# Fuel_Cell_Controller_V1.net
KiCad netlist of a schematic drawn in EAGLE
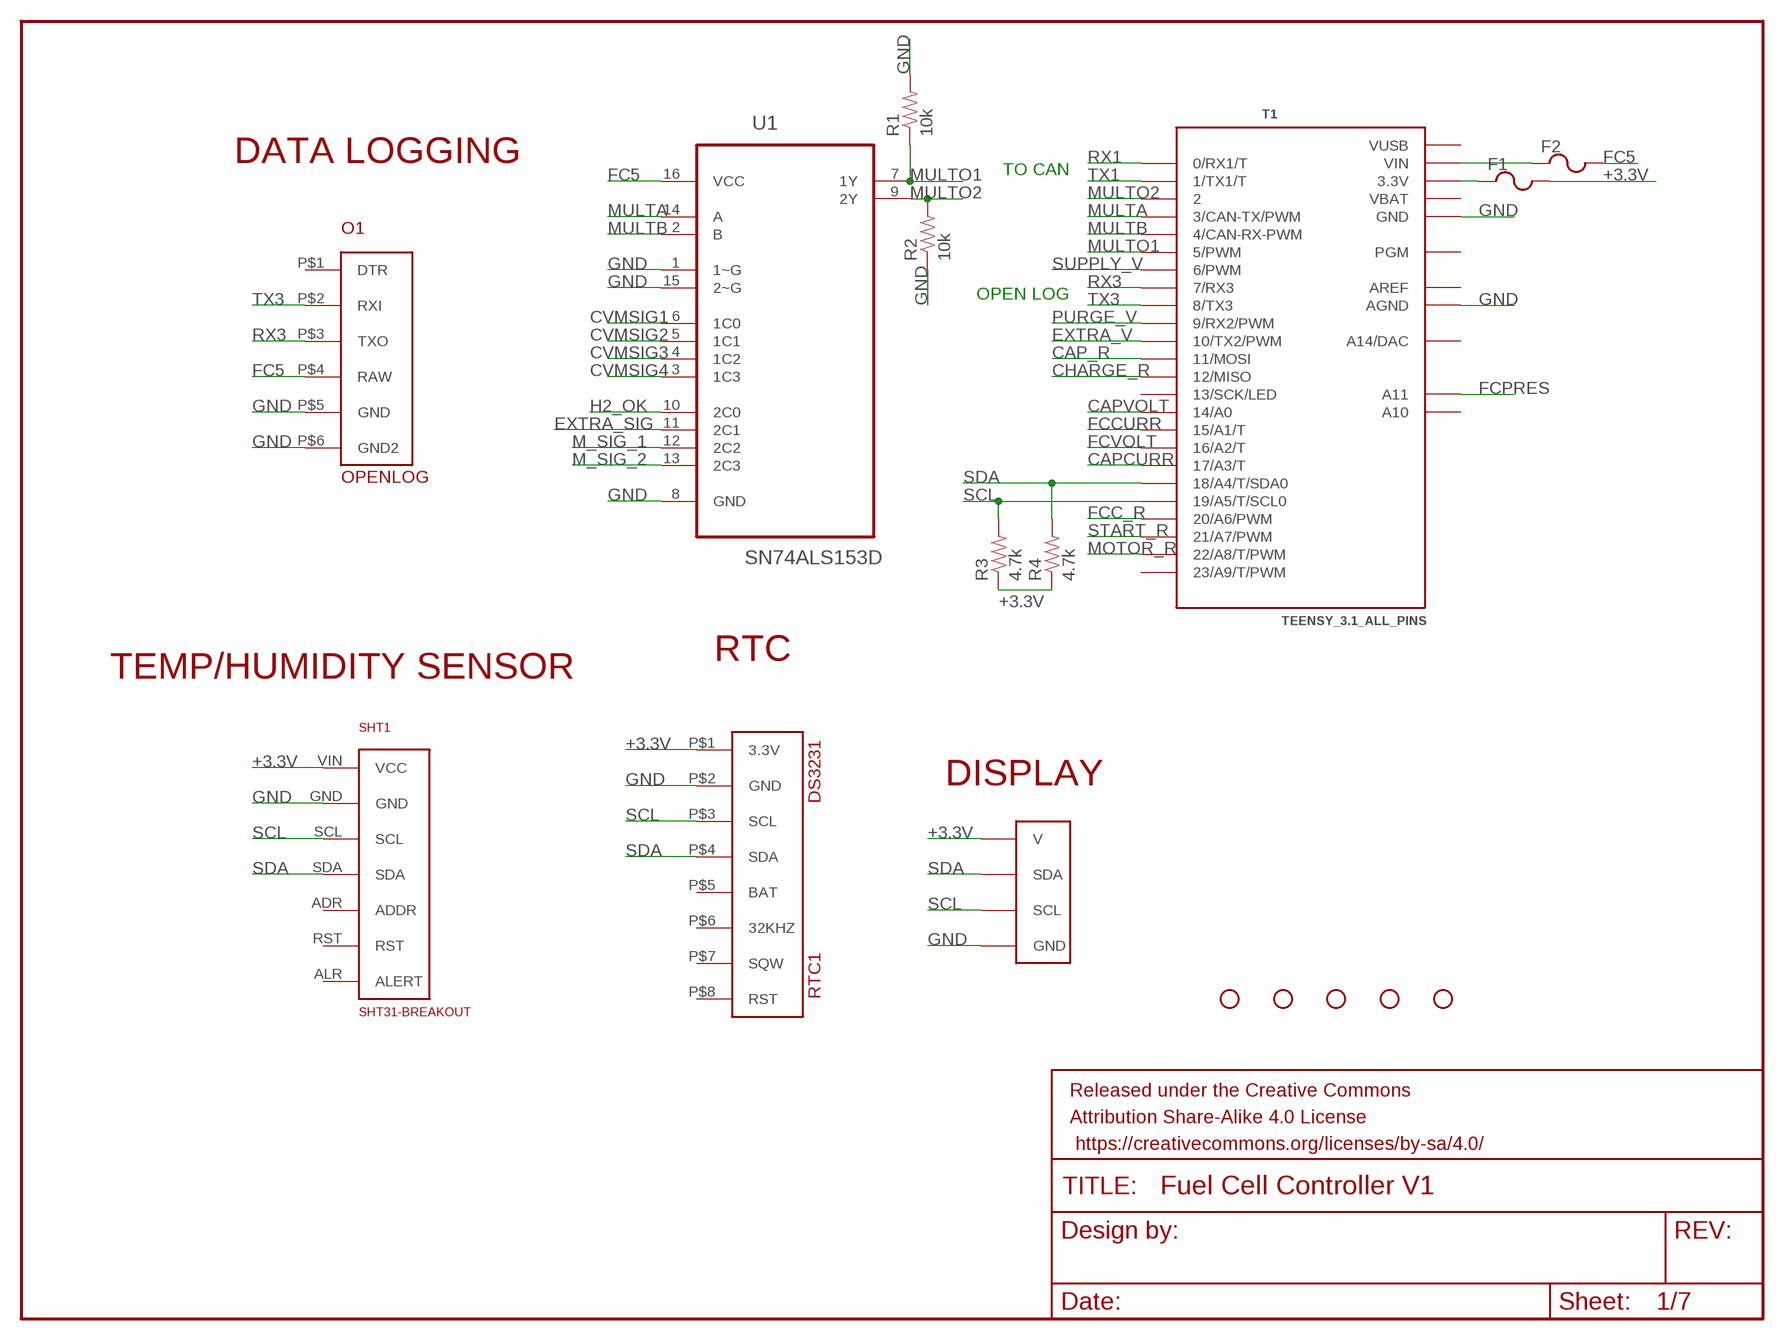
[diagram p0: schematic, sheet 1]
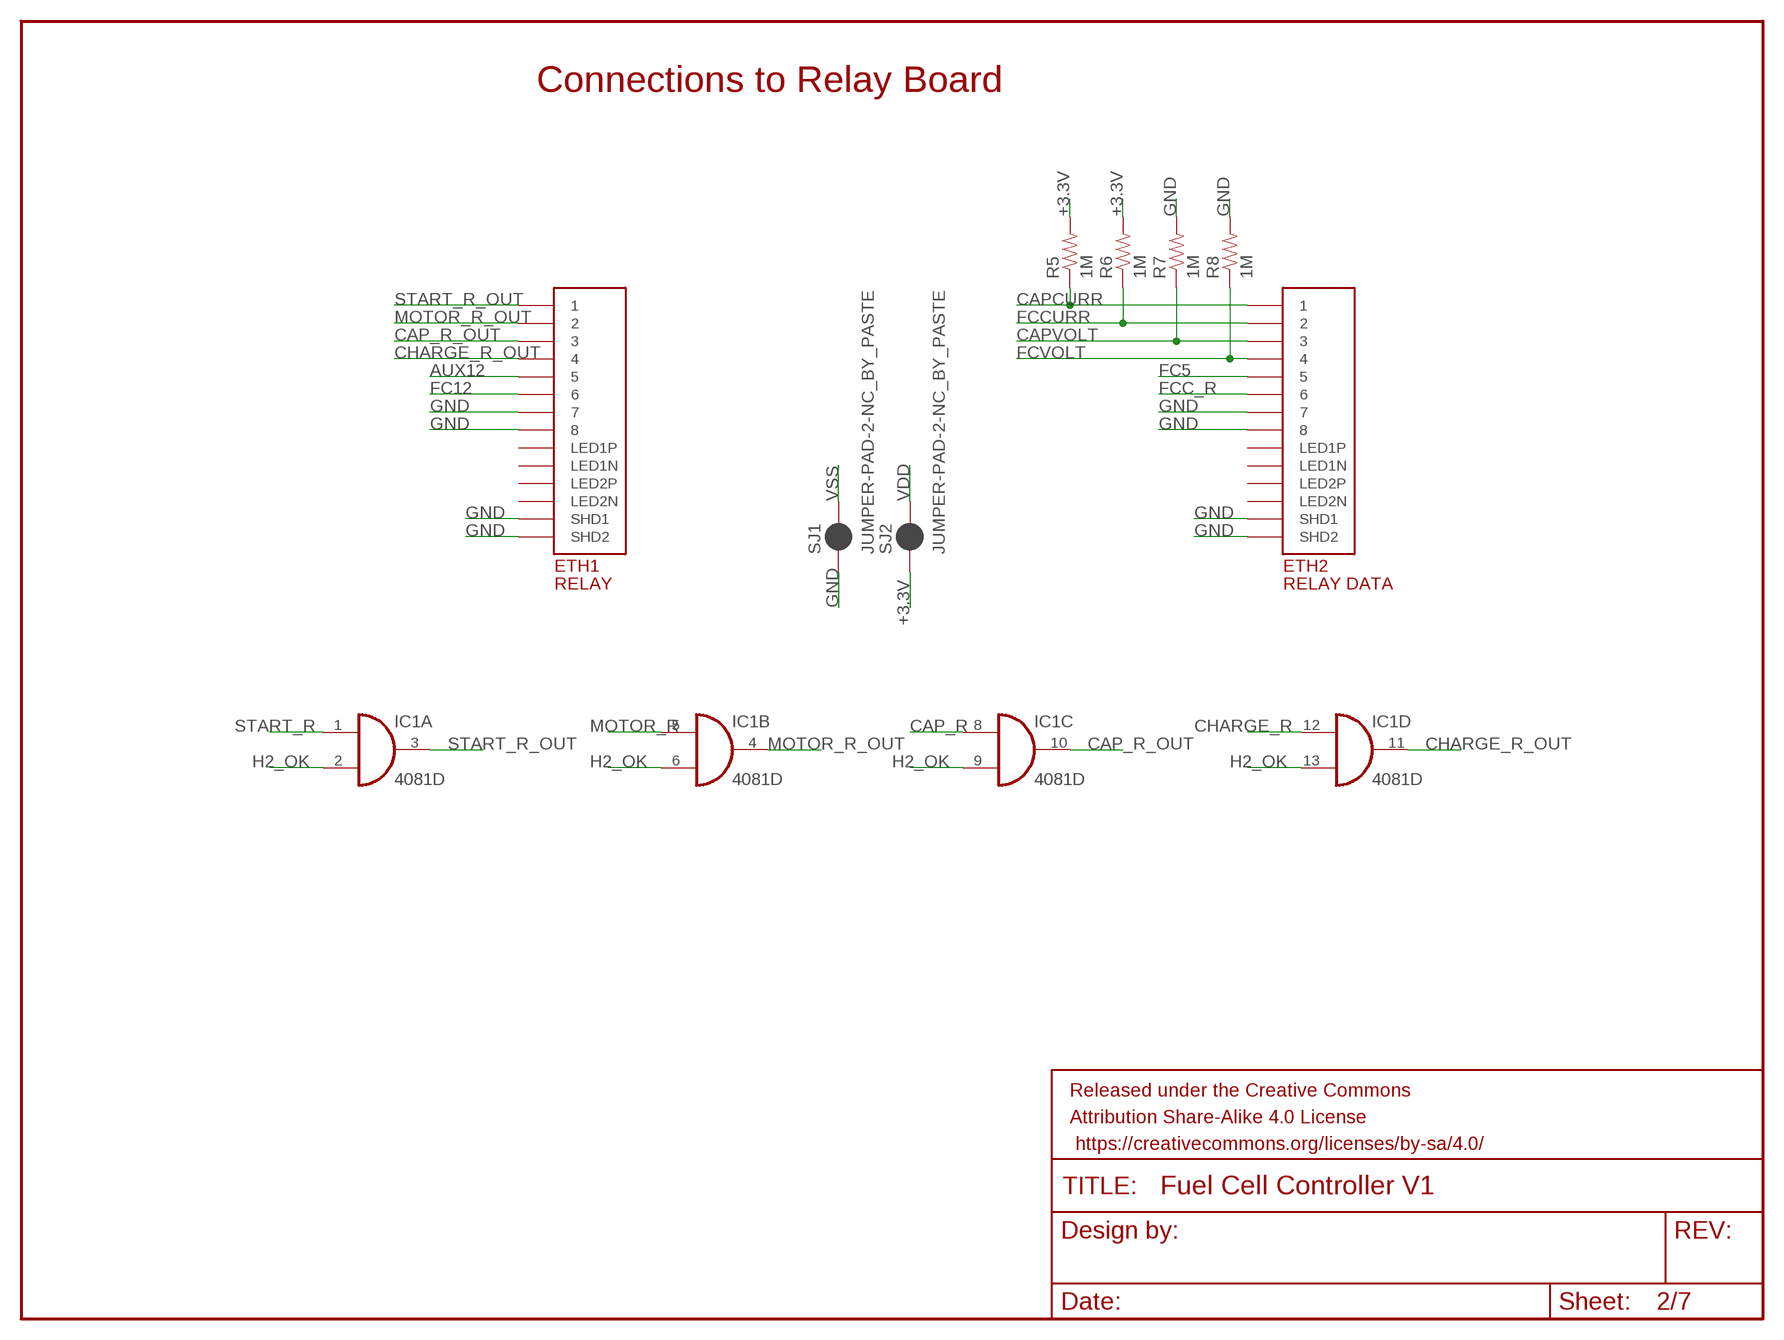
[diagram p1: schematic, sheet 2]
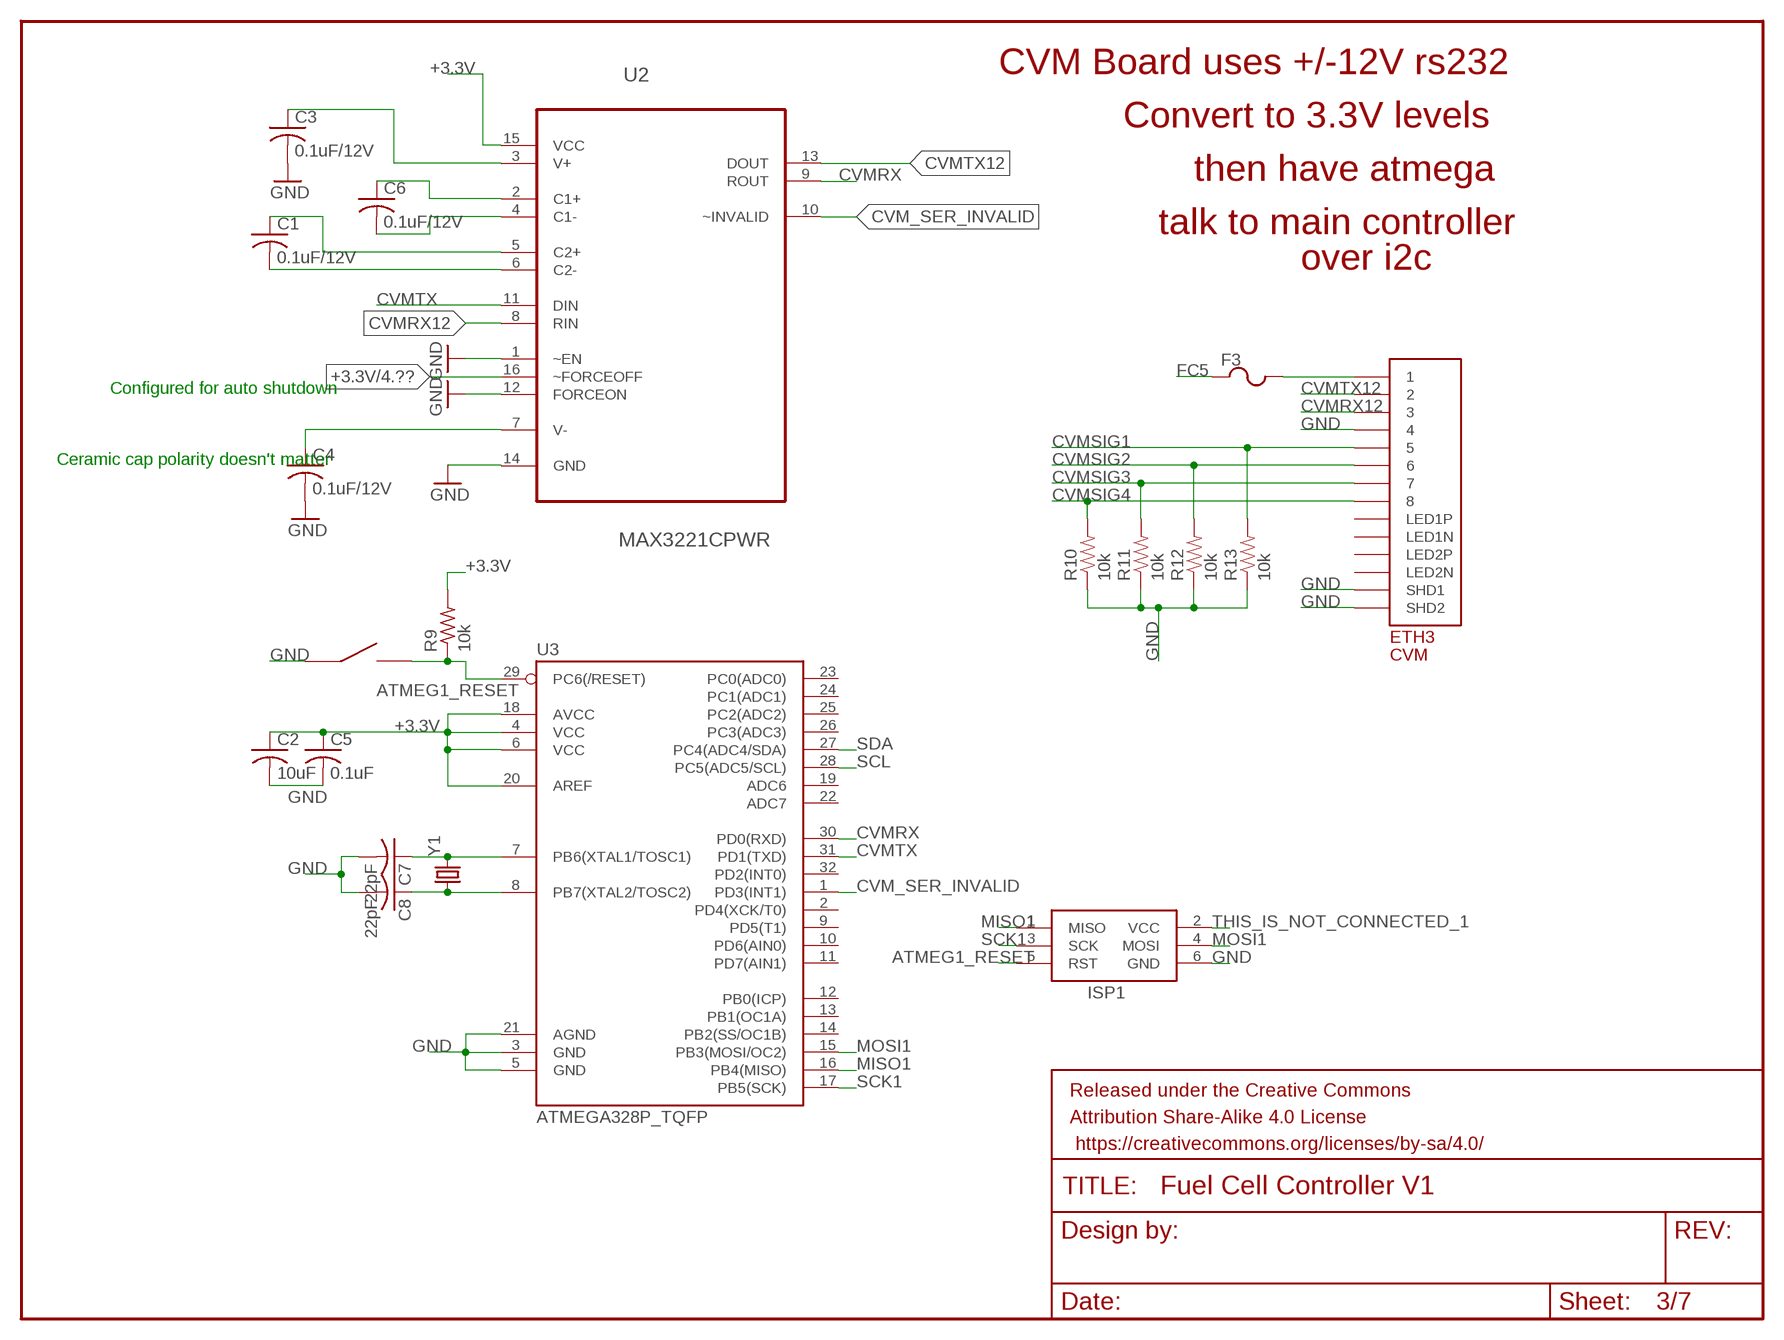
[diagram p2: schematic, sheet 3]
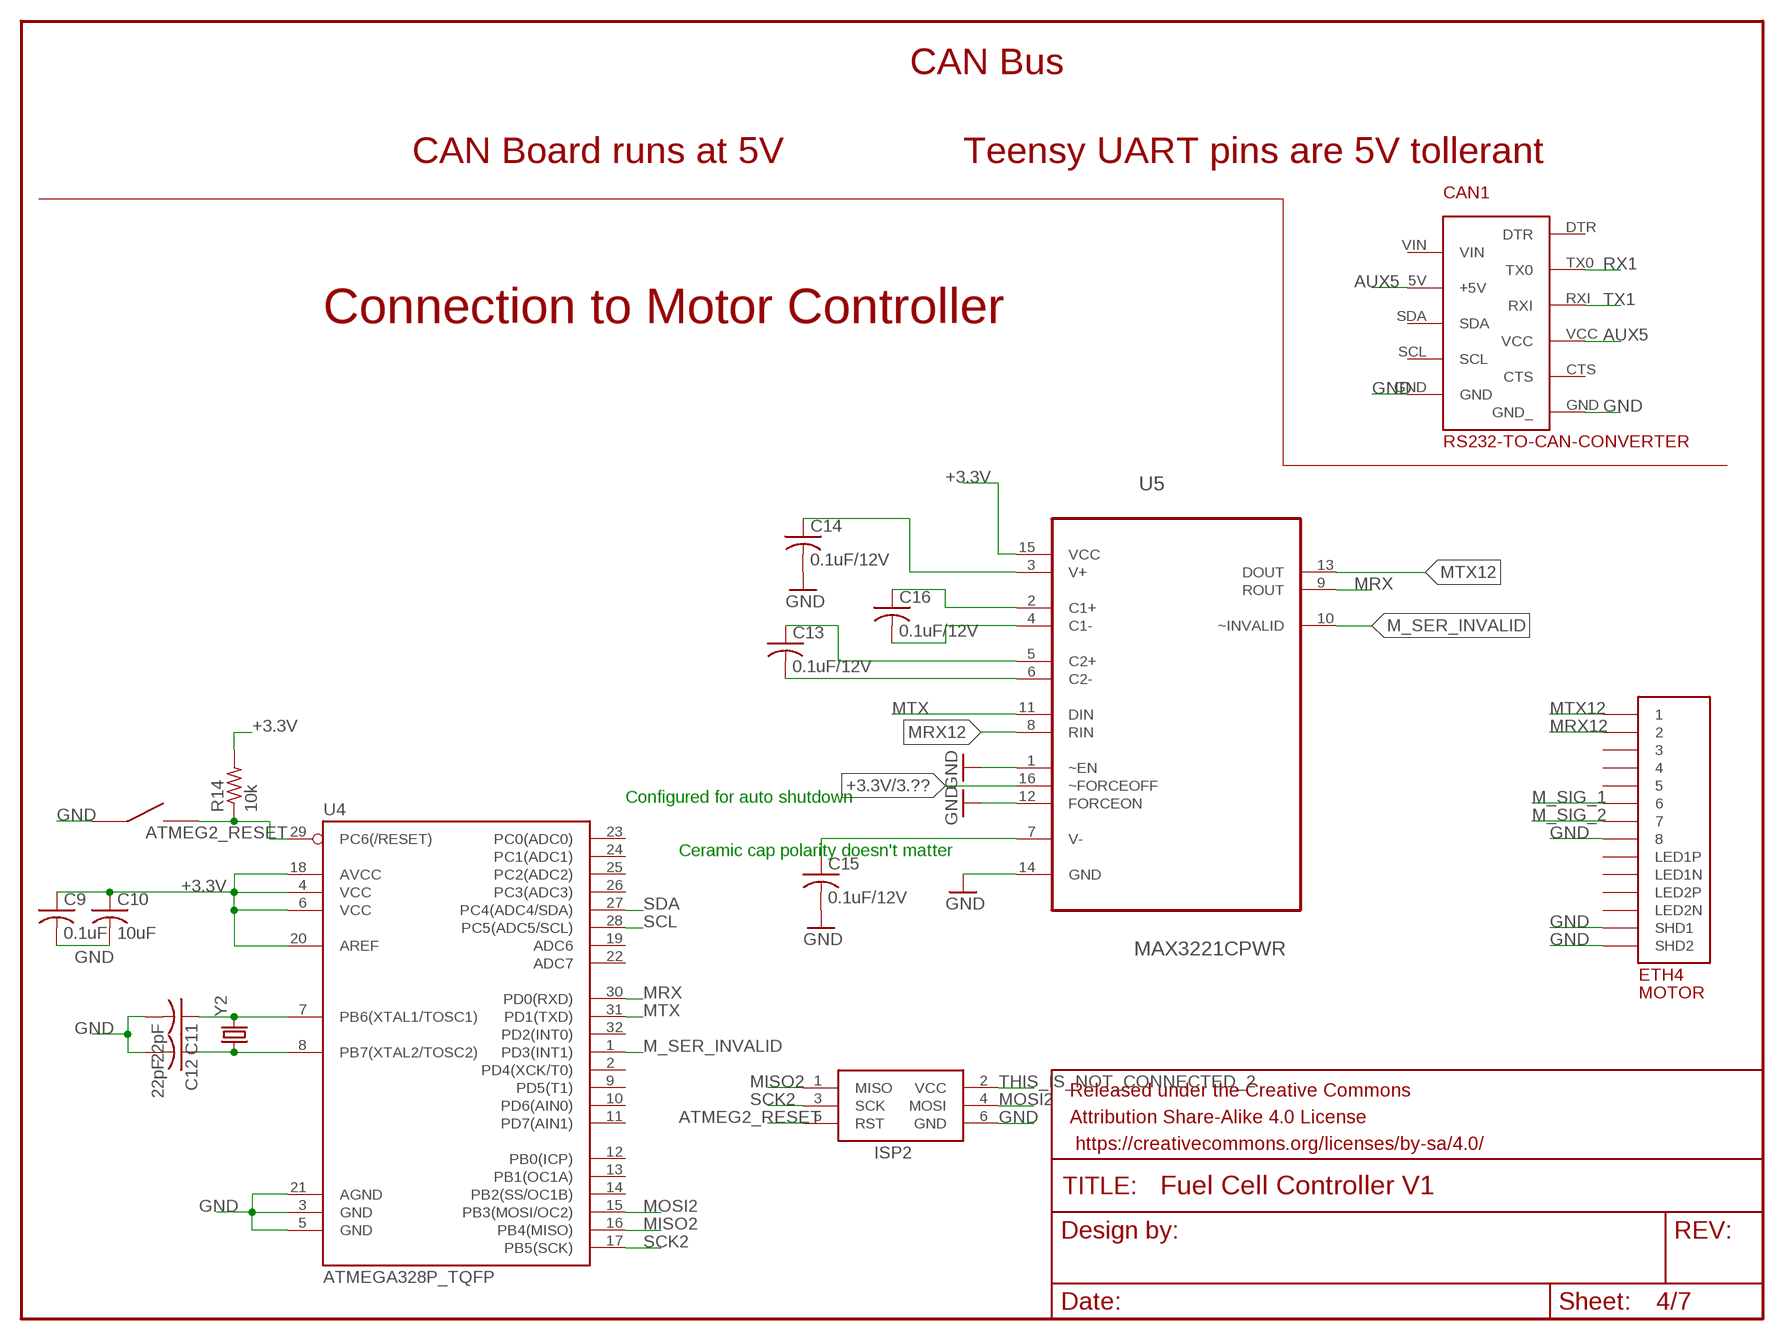
[diagram p3: schematic, sheet 4]
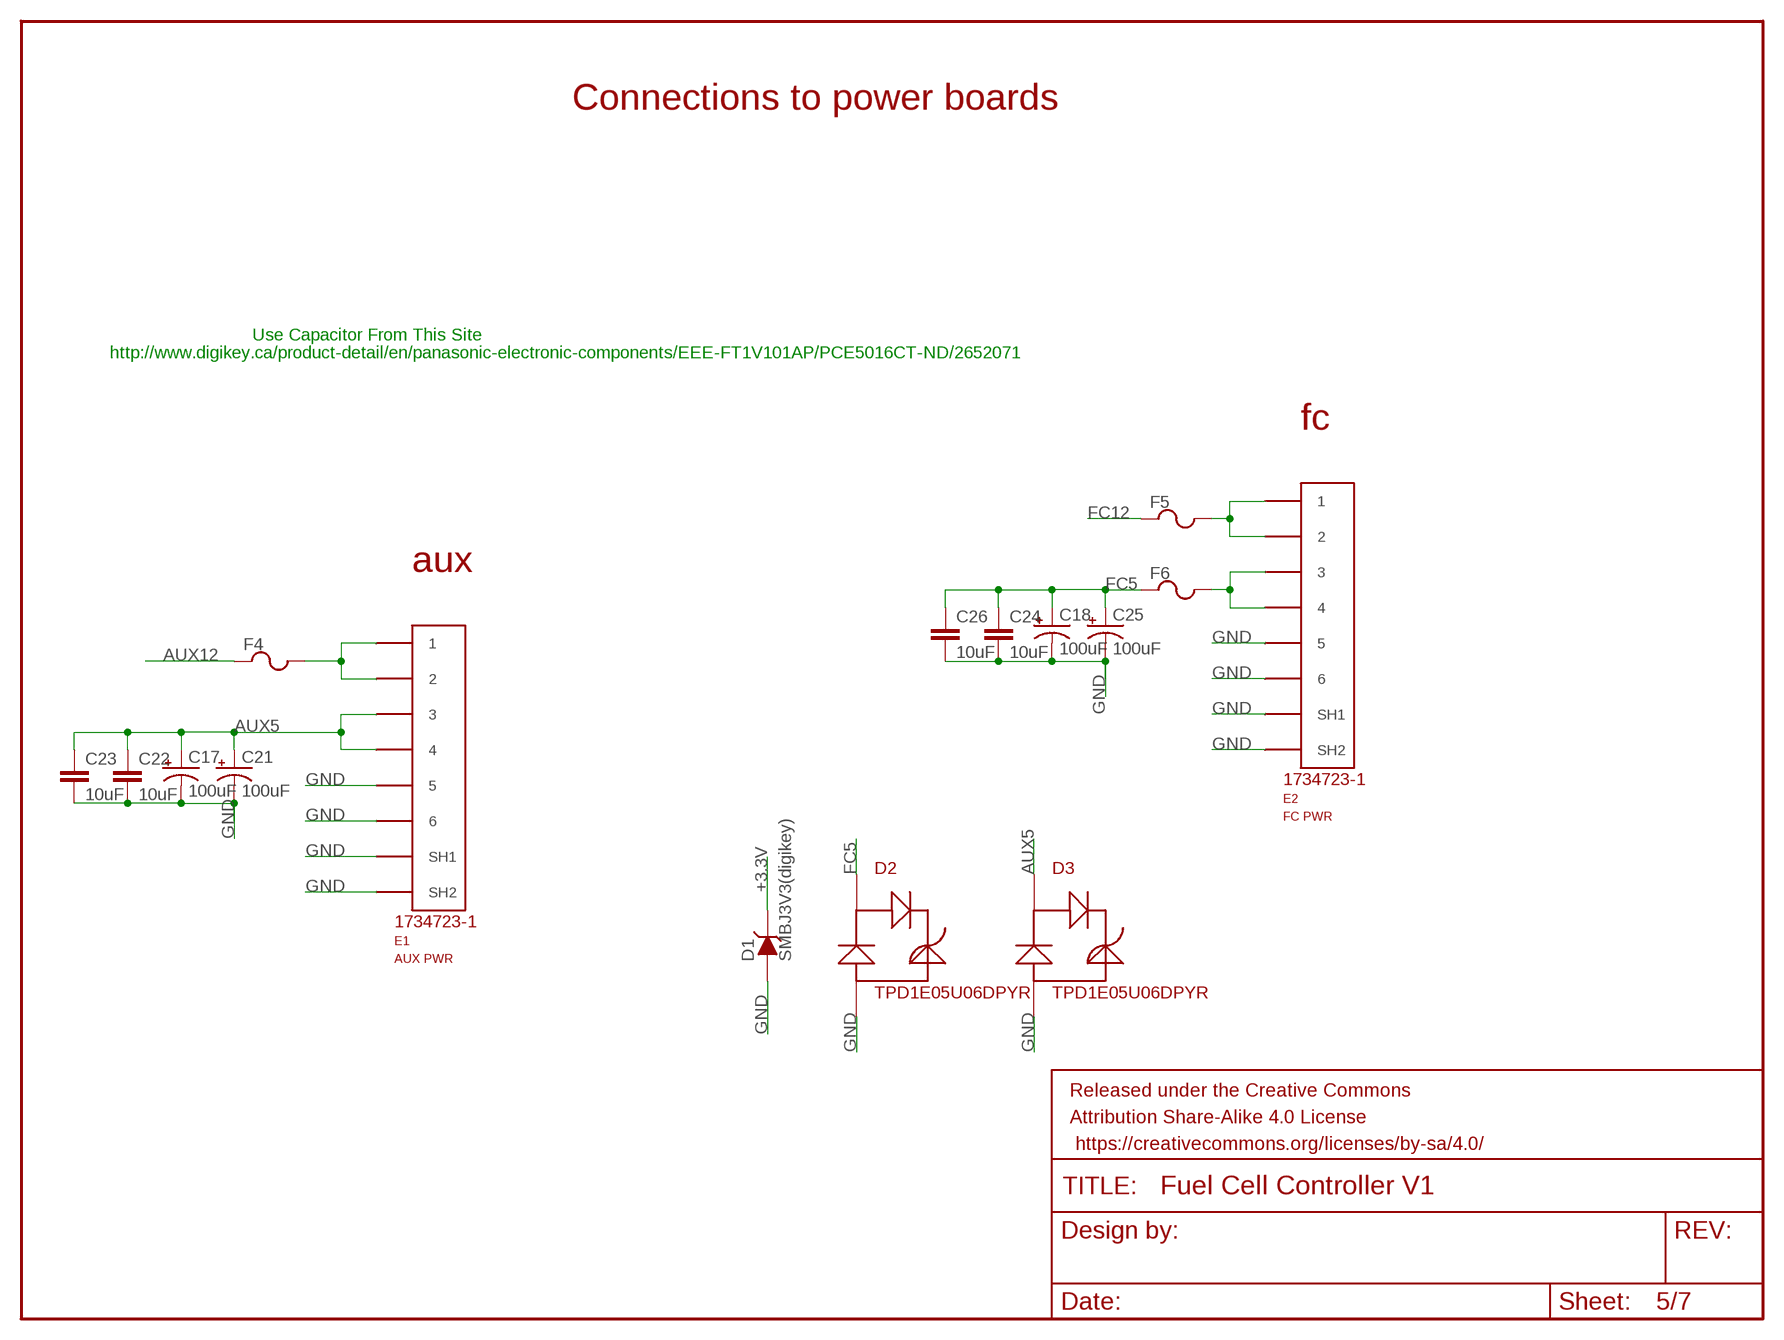
[diagram p4: schematic, sheet 5]
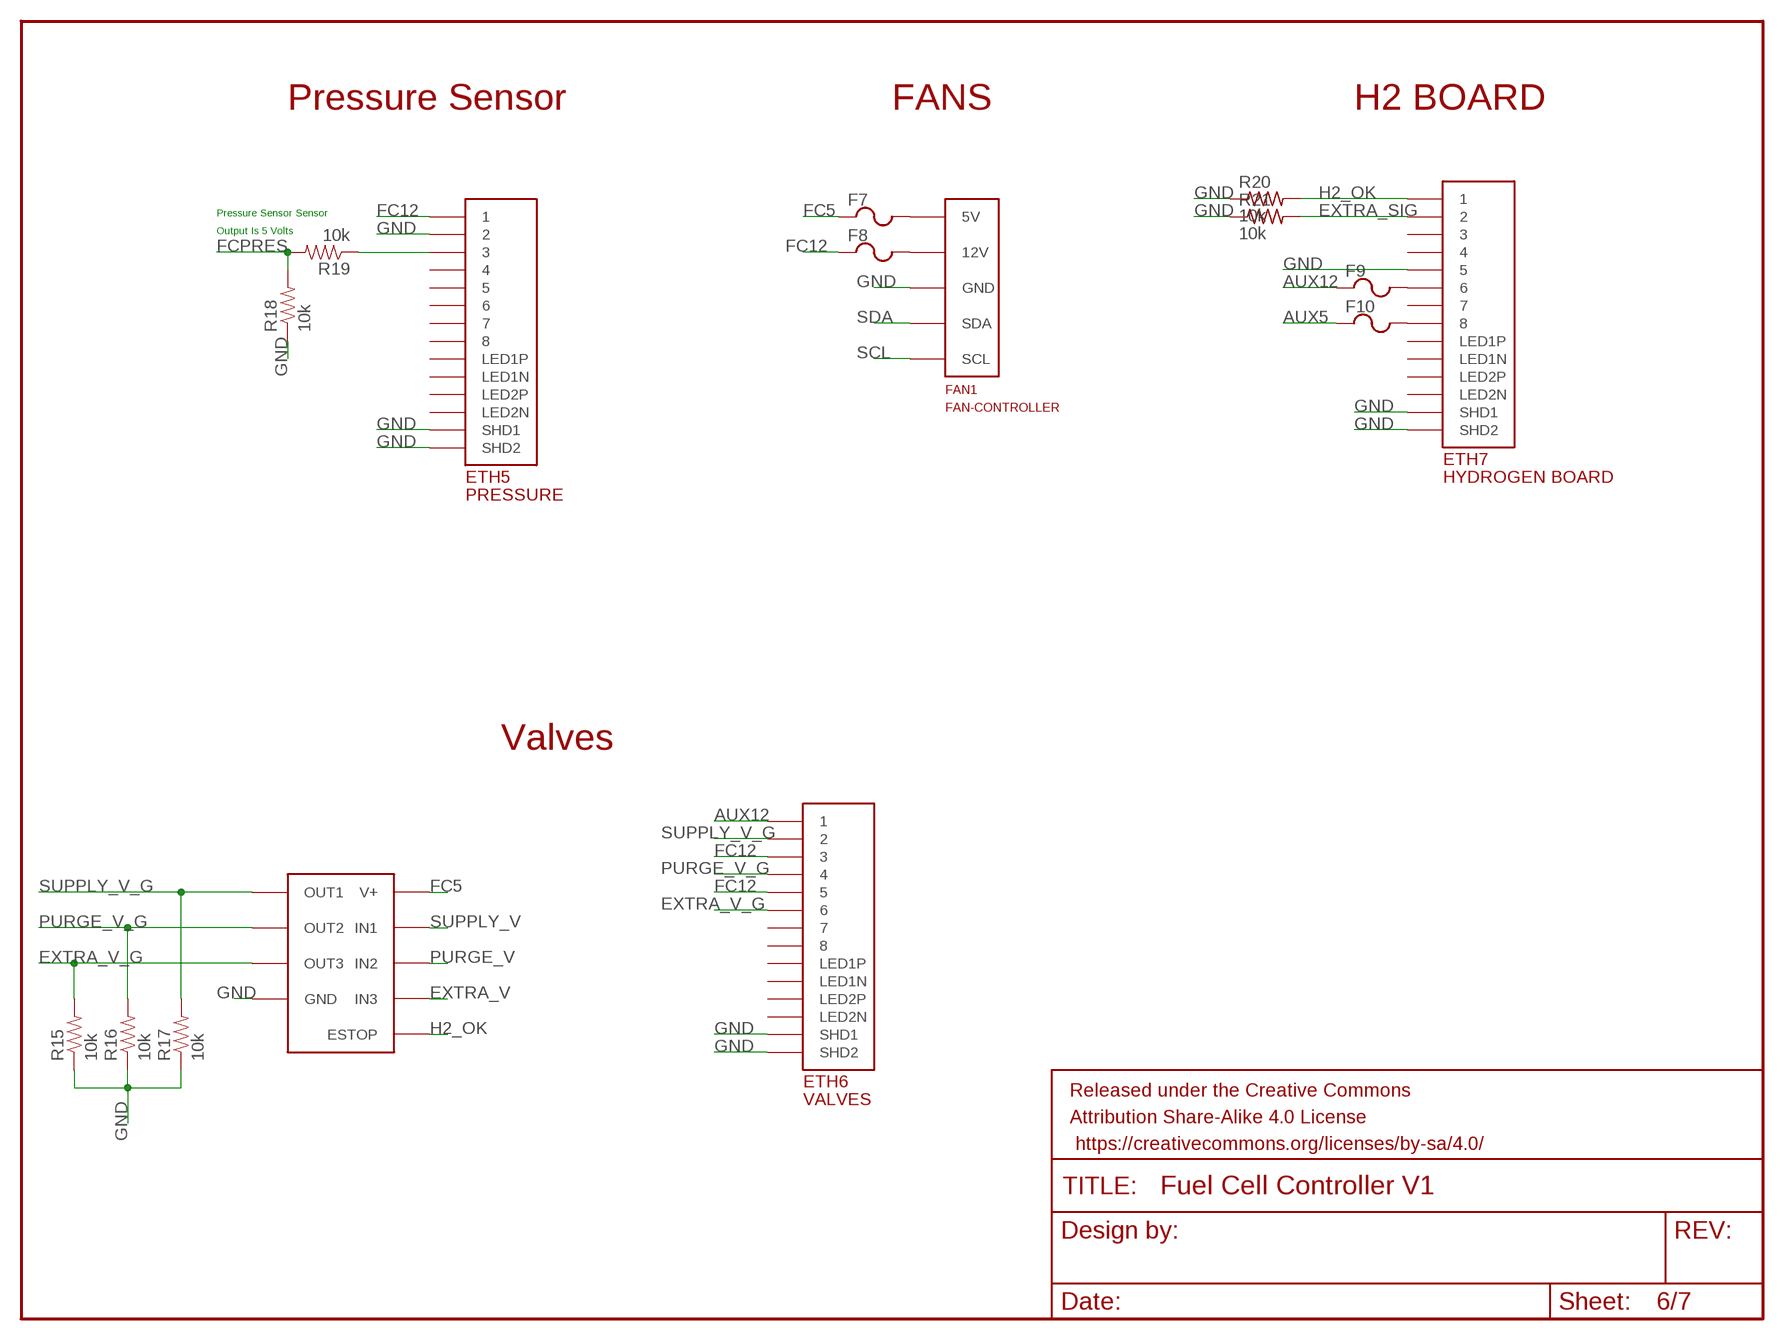
[diagram p5: schematic, sheet 6]
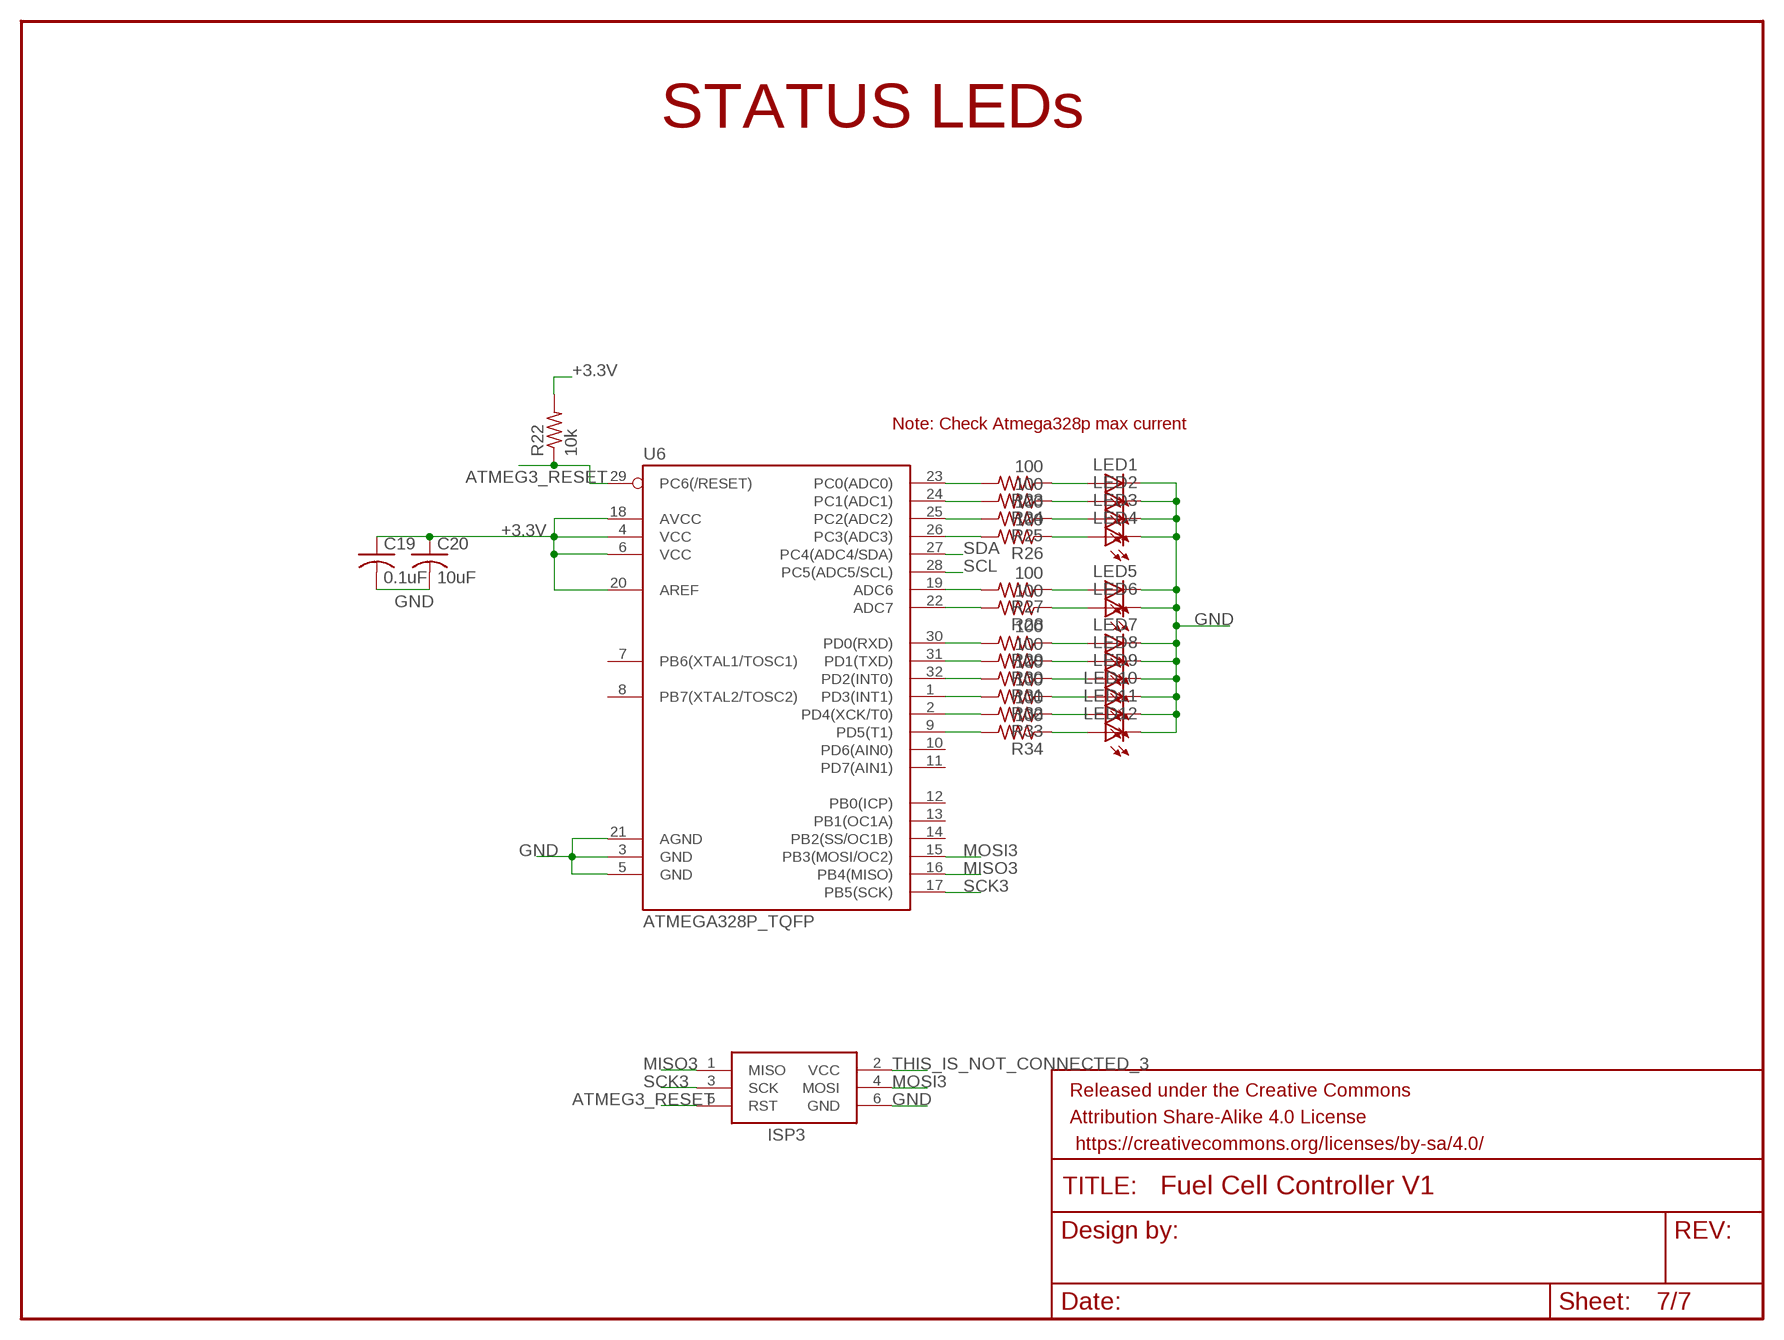
[diagram p6: schematic, sheet 7]

(export (version "E")
  (design (tool "Eeschema 10.0.6"))
  (components
    (comp (ref "F1")
      (value "POLYFUSE")
      (footprint "eagle-import:1206")
      (libsource (lib "eagle-import") (part "POLYFUSE"))
    )
    (comp (ref "F2")
      (value "POLYFUSE")
      (footprint "eagle-import:1206")
      (libsource (lib "eagle-import") (part "POLYFUSE"))
    )
    (comp (ref "FRAME1")
      (value "FRAME-LETTERNO_PACKAGE")
      (footprint "eagle-import:DUMMY")
      (fields (field (name "DESIGNER") "Reegan McAllister"))
      (libsource (lib "eagle-import") (part "FRAME-LETTERNO_PACKAGE"))
    )
    (comp (ref "LCD1")
      (value "LCD-BOARD")
      (footprint "eagle-import:LCD-BOARD")
      (libsource (lib "eagle-import") (part "LCD-BOARD"))
    )
    (comp (ref "O1")
      (value "OPENLOG")
      (footprint "eagle-import:OPENLOG")
      (libsource (lib "eagle-import") (part "OPENLOG"))
    )
    (comp (ref "R1")
      (value "10k")
      (footprint "eagle-import:0805")
      (libsource (lib "eagle-import") (part "RESISTOR0805-RES"))
    )
    (comp (ref "R2")
      (value "10k")
      (footprint "eagle-import:0805")
      (libsource (lib "eagle-import") (part "RESISTOR0805-RES"))
    )
    (comp (ref "R3")
      (value "4.7k")
      (footprint "eagle-import:0805")
      (libsource (lib "eagle-import") (part "RESISTOR0805-RES"))
    )
    (comp (ref "R4")
      (value "4.7k")
      (footprint "eagle-import:0805")
      (libsource (lib "eagle-import") (part "RESISTOR0805-RES"))
    )
    (comp (ref "RTC1")
      (value "DS3231")
      (footprint "eagle-import:DS3231")
      (libsource (lib "eagle-import") (part "DS3231"))
    )
    (comp (ref "SHT1")
      (value "SHT31-BREAKOUT")
      (footprint "eagle-import:SHT31-BREAKOUT")
      (libsource (lib "eagle-import") (part "SHT31-BREAKOUT"))
    )
    (comp (ref "STANDOFF1")
      (value "STAND-OFF")
      (footprint "eagle-import:STAND-OFF")
      (libsource (lib "eagle-import") (part "STAND-OFF"))
    )
    (comp (ref "STANDOFF2")
      (value "STAND-OFF")
      (footprint "eagle-import:STAND-OFF")
      (libsource (lib "eagle-import") (part "STAND-OFF"))
    )
    (comp (ref "STANDOFF3")
      (value "STAND-OFF")
      (footprint "eagle-import:STAND-OFF")
      (libsource (lib "eagle-import") (part "STAND-OFF"))
    )
    (comp (ref "STANDOFF4")
      (value "STAND-OFF")
      (footprint "eagle-import:STAND-OFF")
      (libsource (lib "eagle-import") (part "STAND-OFF"))
    )
    (comp (ref "STANDOFF5")
      (value "STAND-OFF")
      (footprint "eagle-import:STAND-OFF")
      (libsource (lib "eagle-import") (part "STAND-OFF"))
    )
    (comp (ref "T1")
      (value "TEENSY_3.1_ALL_PINS")
      (footprint "eagle-import:TEENSY3-ALL_PINS")
      (libsource (lib "eagle-import") (part "TEENSY_3.1_ALL_PINS"))
    )
    (comp (ref "U1")
      (value "SN74ALS153D")
      (footprint "eagle-import:SOIC127P600X175-16N")
      (libsource (lib "eagle-import") (part "SN74ALS153D"))
    )
    (comp (ref "C17")
      (value "100uF")
      (footprint "eagle-import:PANASONIC_D")
      (libsource (lib "eagle-import") (part "CAP_POLD"))
    )
    (comp (ref "C18")
      (value "100uF")
      (footprint "eagle-import:PANASONIC_D")
      (libsource (lib "eagle-import") (part "CAP_POLD"))
    )
    (comp (ref "C21")
      (value "100uF")
      (footprint "eagle-import:PANASONIC_D")
      (libsource (lib "eagle-import") (part "CAP_POLD"))
    )
    (comp (ref "C22")
      (value "10uF")
      (footprint "eagle-import:0805")
      (libsource (lib "eagle-import") (part "CAP0805"))
    )
    (comp (ref "C23")
      (value "10uF")
      (footprint "eagle-import:0805")
      (libsource (lib "eagle-import") (part "CAP0805"))
    )
    (comp (ref "C24")
      (value "10uF")
      (footprint "eagle-import:0805")
      (libsource (lib "eagle-import") (part "CAP0805"))
    )
    (comp (ref "C25")
      (value "100uF")
      (footprint "eagle-import:PANASONIC_D")
      (libsource (lib "eagle-import") (part "CAP_POLD"))
    )
    (comp (ref "C26")
      (value "10uF")
      (footprint "eagle-import:0805")
      (libsource (lib "eagle-import") (part "CAP0805"))
    )
    (comp (ref "D1")
      (value "SMBJ3V3(digikey)")
      (footprint "eagle-import:DO-214AB")
      (libsource (lib "eagle-import") (part "5KASMC"))
    )
    (comp (ref "D2")
      (value "TPD1E05U06DPYR")
      (footprint "eagle-import:2-XDFN")
      (libsource (lib "eagle-import") (part "TPD1E05U06DPYR"))
    )
    (comp (ref "D3")
      (value "TPD1E05U06DPYR")
      (footprint "eagle-import:2-XDFN")
      (libsource (lib "eagle-import") (part "TPD1E05U06DPYR"))
    )
    (comp (ref "E1")
      (value "AUX PWR")
      (footprint "eagle-import:1734723-1_RJ11")
      (libsource (lib "eagle-import") (part "5555140-6"))
    )
    (comp (ref "E2")
      (value "FC PWR")
      (footprint "eagle-import:1734723-1_RJ11")
      (libsource (lib "eagle-import") (part "5555140-6"))
    )
    (comp (ref "F4")
      (value "POLYFUSE")
      (footprint "eagle-import:1206")
      (libsource (lib "eagle-import") (part "POLYFUSE"))
    )
    (comp (ref "F5")
      (value "POLYFUSE")
      (footprint "eagle-import:1206")
      (libsource (lib "eagle-import") (part "POLYFUSE"))
    )
    (comp (ref "F6")
      (value "POLYFUSE")
      (footprint "eagle-import:1206")
      (libsource (lib "eagle-import") (part "POLYFUSE"))
    )
    (comp (ref "FRAME5")
      (value "FRAME-LETTERNO_PACKAGE")
      (footprint "eagle-import:DUMMY")
      (fields (field (name "DESIGNER") "Nobody"))
      (libsource (lib "eagle-import") (part "FRAME-LETTERNO_PACKAGE"))
    )
    (comp (ref "ETH5")
      (value "PRESSURE")
      (footprint "eagle-import:A122645-ND")
      (libsource (lib "eagle-import") (part "ETHERNET"))
    )
    (comp (ref "ETH6")
      (value "VALVES")
      (footprint "eagle-import:A122645-ND")
      (libsource (lib "eagle-import") (part "ETHERNET"))
    )
    (comp (ref "ETH7")
      (value "HYDROGEN BOARD")
      (footprint "eagle-import:A122645-ND")
      (libsource (lib "eagle-import") (part "ETHERNET"))
    )
    (comp (ref "F7")
      (value "POLYFUSE")
      (footprint "eagle-import:1206")
      (libsource (lib "eagle-import") (part "POLYFUSE"))
    )
    (comp (ref "F8")
      (value "POLYFUSE")
      (footprint "eagle-import:1206")
      (libsource (lib "eagle-import") (part "POLYFUSE"))
    )
    (comp (ref "F9")
      (value "POLYFUSE")
      (footprint "eagle-import:1206")
      (libsource (lib "eagle-import") (part "POLYFUSE"))
    )
    (comp (ref "F10")
      (value "POLYFUSE")
      (footprint "eagle-import:1206")
      (libsource (lib "eagle-import") (part "POLYFUSE"))
    )
    (comp (ref "FAN1")
      (value "FAN-CONTROLLER")
      (footprint "eagle-import:FAN-CONTROLLER")
      (libsource (lib "eagle-import") (part "FAN-CONTROLLER"))
    )
    (comp (ref "FRAME6")
      (value "FRAME-LETTERNO_PACKAGE")
      (footprint "eagle-import:DUMMY")
      (fields (field (name "DESIGNER") "Nobody"))
      (libsource (lib "eagle-import") (part "FRAME-LETTERNO_PACKAGE"))
    )
    (comp (ref "M1")
      (value "MOSFETBOARD")
      (footprint "eagle-import:MOSFET-BOARD")
      (libsource (lib "eagle-import") (part "MOSFETBOARD"))
    )
    (comp (ref "R15")
      (value "10k")
      (footprint "eagle-import:0805")
      (libsource (lib "eagle-import") (part "RESISTOR0805-RES"))
    )
    (comp (ref "R16")
      (value "10k")
      (footprint "eagle-import:0805")
      (libsource (lib "eagle-import") (part "RESISTOR0805-RES"))
    )
    (comp (ref "R17")
      (value "10k")
      (footprint "eagle-import:0805")
      (libsource (lib "eagle-import") (part "RESISTOR0805-RES"))
    )
    (comp (ref "R18")
      (value "10k")
      (footprint "eagle-import:0805")
      (libsource (lib "eagle-import") (part "RESISTOR0805-RES"))
    )
    (comp (ref "R19")
      (value "10k")
      (footprint "eagle-import:0805")
      (libsource (lib "eagle-import") (part "RESISTOR0805-RES"))
    )
    (comp (ref "R20")
      (value "10k")
      (footprint "eagle-import:R0603")
      (libsource (lib "eagle-import") (part "R-US_R0603"))
    )
    (comp (ref "R21")
      (value "10k")
      (footprint "eagle-import:R0603")
      (libsource (lib "eagle-import") (part "R-US_R0603"))
    )
    (comp (ref "C19")
      (value "0.1uF")
      (footprint "eagle-import:C0603")
      (libsource (lib "eagle-import") (part "adafruit_C-USC0603"))
    )
    (comp (ref "C20")
      (value "10uF")
      (footprint "eagle-import:C0603")
      (libsource (lib "eagle-import") (part "adafruit_C-USC0603"))
    )
    (comp (ref "FRAME7")
      (value "FRAME-LETTERNO_PACKAGE")
      (footprint "eagle-import:DUMMY")
      (fields (field (name "DESIGNER") "Nobody"))
      (libsource (lib "eagle-import") (part "FRAME-LETTERNO_PACKAGE"))
    )
    (comp (ref "ISP3")
      (value "AVRISP-BOX")
      (footprint "eagle-import:AVRISP-BOX")
      (libsource (lib "eagle-import") (part "AVRISP-BOX"))
    )
    (comp (ref "LED1")
      (value "LEDCHIPLED_0805")
      (footprint "eagle-import:CHIPLED_0805")
      (libsource (lib "eagle-import") (part "LEDCHIPLED_0805"))
    )
    (comp (ref "LED2")
      (value "LEDCHIPLED_0805")
      (footprint "eagle-import:CHIPLED_0805")
      (libsource (lib "eagle-import") (part "LEDCHIPLED_0805"))
    )
    (comp (ref "LED3")
      (value "LEDCHIPLED_0805")
      (footprint "eagle-import:CHIPLED_0805")
      (libsource (lib "eagle-import") (part "LEDCHIPLED_0805"))
    )
    (comp (ref "LED4")
      (value "LEDCHIPLED_0805")
      (footprint "eagle-import:CHIPLED_0805")
      (libsource (lib "eagle-import") (part "LEDCHIPLED_0805"))
    )
    (comp (ref "LED5")
      (value "LEDCHIPLED_0805")
      (footprint "eagle-import:CHIPLED_0805")
      (libsource (lib "eagle-import") (part "LEDCHIPLED_0805"))
    )
    (comp (ref "LED6")
      (value "LEDCHIPLED_0805")
      (footprint "eagle-import:CHIPLED_0805")
      (libsource (lib "eagle-import") (part "LEDCHIPLED_0805"))
    )
    (comp (ref "LED7")
      (value "LEDCHIPLED_0805")
      (footprint "eagle-import:CHIPLED_0805")
      (libsource (lib "eagle-import") (part "LEDCHIPLED_0805"))
    )
    (comp (ref "LED8")
      (value "LEDCHIPLED_0805")
      (footprint "eagle-import:CHIPLED_0805")
      (libsource (lib "eagle-import") (part "LEDCHIPLED_0805"))
    )
    (comp (ref "LED9")
      (value "LEDCHIPLED_0805")
      (footprint "eagle-import:CHIPLED_0805")
      (libsource (lib "eagle-import") (part "LEDCHIPLED_0805"))
    )
    (comp (ref "LED10")
      (value "LEDCHIPLED_0805")
      (footprint "eagle-import:CHIPLED_0805")
      (libsource (lib "eagle-import") (part "LEDCHIPLED_0805"))
    )
    (comp (ref "LED11")
      (value "LEDCHIPLED_0805")
      (footprint "eagle-import:CHIPLED_0805")
      (libsource (lib "eagle-import") (part "LEDCHIPLED_0805"))
    )
    (comp (ref "LED12")
      (value "LEDCHIPLED_0805")
      (footprint "eagle-import:CHIPLED_0805")
      (libsource (lib "eagle-import") (part "LEDCHIPLED_0805"))
    )
    (comp (ref "R22")
      (value "10k")
      (footprint "eagle-import:R0603")
      (libsource (lib "eagle-import") (part "R-US_R0603"))
    )
    (comp (ref "R23")
      (value "100")
      (footprint "eagle-import:R0603")
      (libsource (lib "eagle-import") (part "R-US_R0603"))
    )
    (comp (ref "R24")
      (value "100")
      (footprint "eagle-import:R0603")
      (libsource (lib "eagle-import") (part "R-US_R0603"))
    )
    (comp (ref "R25")
      (value "100")
      (footprint "eagle-import:R0603")
      (libsource (lib "eagle-import") (part "R-US_R0603"))
    )
    (comp (ref "R26")
      (value "100")
      (footprint "eagle-import:R0603")
      (libsource (lib "eagle-import") (part "R-US_R0603"))
    )
    (comp (ref "R27")
      (value "100")
      (footprint "eagle-import:R0603")
      (libsource (lib "eagle-import") (part "R-US_R0603"))
    )
    (comp (ref "R28")
      (value "100")
      (footprint "eagle-import:R0603")
      (libsource (lib "eagle-import") (part "R-US_R0603"))
    )
    (comp (ref "R29")
      (value "100")
      (footprint "eagle-import:R0603")
      (libsource (lib "eagle-import") (part "R-US_R0603"))
    )
    (comp (ref "R30")
      (value "100")
      (footprint "eagle-import:R0603")
      (libsource (lib "eagle-import") (part "R-US_R0603"))
    )
    (comp (ref "R31")
      (value "100")
      (footprint "eagle-import:R0603")
      (libsource (lib "eagle-import") (part "R-US_R0603"))
    )
    (comp (ref "R32")
      (value "100")
      (footprint "eagle-import:R0603")
      (libsource (lib "eagle-import") (part "R-US_R0603"))
    )
    (comp (ref "R33")
      (value "100")
      (footprint "eagle-import:R0603")
      (libsource (lib "eagle-import") (part "R-US_R0603"))
    )
    (comp (ref "R34")
      (value "100")
      (footprint "eagle-import:R0603")
      (libsource (lib "eagle-import") (part "R-US_R0603"))
    )
    (comp (ref "U6")
      (value "ATMEGA328P_TQFP")
      (footprint "eagle-import:TQFP32-08")
      (libsource (lib "eagle-import") (part "ATMEGA328P_TQFP"))
    )
    (comp (ref "C9")
      (value "0.1uF")
      (footprint "eagle-import:C0603")
      (libsource (lib "eagle-import") (part "adafruit_C-USC0603"))
    )
    (comp (ref "C10")
      (value "10uF")
      (footprint "eagle-import:C0603")
      (libsource (lib "eagle-import") (part "adafruit_C-USC0603"))
    )
    (comp (ref "C11")
      (value "22pF")
      (footprint "eagle-import:C0603")
      (libsource (lib "eagle-import") (part "adafruit_C-USC0603"))
    )
    (comp (ref "C12")
      (value "22pF")
      (footprint "eagle-import:C0603")
      (libsource (lib "eagle-import") (part "adafruit_C-USC0603"))
    )
    (comp (ref "C13")
      (value "0.1uF/12V")
      (footprint "eagle-import:C0805")
      (libsource (lib "eagle-import") (part "C-USC0805"))
    )
    (comp (ref "C14")
      (value "0.1uF/12V")
      (footprint "eagle-import:C0805")
      (libsource (lib "eagle-import") (part "C-USC0805"))
    )
    (comp (ref "C15")
      (value "0.1uF/12V")
      (footprint "eagle-import:C0805")
      (libsource (lib "eagle-import") (part "C-USC0805"))
    )
    (comp (ref "C16")
      (value "0.1uF/12V")
      (footprint "eagle-import:C0805")
      (libsource (lib "eagle-import") (part "C-USC0805"))
    )
    (comp (ref "CAN1")
      (value "RS232-TO-CAN-CONVERTER")
      (footprint "eagle-import:RS232-TO-CAN-CONVERTER")
      (libsource (lib "eagle-import") (part "RS232-TO-CAN-CONVERTER"))
    )
    (comp (ref "ETH4")
      (value "MOTOR")
      (footprint "eagle-import:A122645-ND")
      (libsource (lib "eagle-import") (part "ETHERNET"))
    )
    (comp (ref "FRAME4")
      (value "FRAME-LETTERNO_PACKAGE")
      (footprint "eagle-import:DUMMY")
      (fields (field (name "DESIGNER") "Nobody"))
      (libsource (lib "eagle-import") (part "FRAME-LETTERNO_PACKAGE"))
    )
    (comp (ref "ISP2")
      (value "AVRISP-BOX")
      (footprint "eagle-import:AVRISP-BOX")
      (libsource (lib "eagle-import") (part "AVRISP-BOX"))
    )
    (comp (ref "R14")
      (value "10k")
      (footprint "eagle-import:R0603")
      (libsource (lib "eagle-import") (part "R-US_R0603"))
    )
    (comp (ref "S2")
      (value "EG4621CT-ND")
      (footprint "eagle-import:EG4621CT-ND")
      (libsource (lib "eagle-import") (part "EG4621CT-ND"))
    )
    (comp (ref "U4")
      (value "ATMEGA328P_TQFP")
      (footprint "eagle-import:TQFP32-08")
      (libsource (lib "eagle-import") (part "ATMEGA328P_TQFP"))
    )
    (comp (ref "U5")
      (value "MAX3221CPWR")
      (footprint "eagle-import:SOP65P640X120-16N")
      (libsource (lib "eagle-import") (part "MAX3221CPWR"))
    )
    (comp (ref "Y2")
      (value "CRYSTALHC49US")
      (footprint "eagle-import:HC49US")
      (libsource (lib "eagle-import") (part "CRYSTALHC49US"))
    )
    (comp (ref "ETH1")
      (value "RELAY")
      (footprint "eagle-import:A122645-ND")
      (libsource (lib "eagle-import") (part "ETHERNET"))
    )
    (comp (ref "ETH2")
      (value "RELAY DATA")
      (footprint "eagle-import:A122645-ND")
      (libsource (lib "eagle-import") (part "ETHERNET"))
    )
    (comp (ref "FRAME2")
      (value "FRAME-LETTERNO_PACKAGE")
      (footprint "eagle-import:DUMMY")
      (fields (field (name "DESIGNER") "Nobody"))
      (libsource (lib "eagle-import") (part "FRAME-LETTERNO_PACKAGE"))
    )
    (comp (ref "IC1")
      (value "4081D")
      (footprint "eagle-import:SO14")
      (libsource (lib "eagle-import") (part "4081D"))
    )
    (comp (ref "R5")
      (value "1M")
      (footprint "eagle-import:0805")
      (libsource (lib "eagle-import") (part "RESISTOR0805-RES"))
    )
    (comp (ref "R6")
      (value "1M")
      (footprint "eagle-import:0805")
      (libsource (lib "eagle-import") (part "RESISTOR0805-RES"))
    )
    (comp (ref "R7")
      (value "1M")
      (footprint "eagle-import:0805")
      (libsource (lib "eagle-import") (part "RESISTOR0805-RES"))
    )
    (comp (ref "R8")
      (value "1M")
      (footprint "eagle-import:0805")
      (libsource (lib "eagle-import") (part "RESISTOR0805-RES"))
    )
    (comp (ref "SJ1")
      (value "JUMPER-PAD-2-NC_BY_PASTE")
      (footprint "eagle-import:PAD-JUMPER-2-NC_BY_PASTE_YES_SILK")
      (libsource (lib "eagle-import") (part "JUMPER-PAD-2-NC_BY_PASTE"))
    )
    (comp (ref "SJ2")
      (value "JUMPER-PAD-2-NC_BY_PASTE")
      (footprint "eagle-import:PAD-JUMPER-2-NC_BY_PASTE_YES_SILK")
      (libsource (lib "eagle-import") (part "JUMPER-PAD-2-NC_BY_PASTE"))
    )
    (comp (ref "C1")
      (value "0.1uF/12V")
      (footprint "eagle-import:C0805")
      (libsource (lib "eagle-import") (part "C-USC0805"))
    )
    (comp (ref "C2")
      (value "10uF")
      (footprint "eagle-import:C0603")
      (libsource (lib "eagle-import") (part "adafruit_C-USC0603"))
    )
    (comp (ref "C3")
      (value "0.1uF/12V")
      (footprint "eagle-import:C0805")
      (libsource (lib "eagle-import") (part "C-USC0805"))
    )
    (comp (ref "C4")
      (value "0.1uF/12V")
      (footprint "eagle-import:C0805")
      (libsource (lib "eagle-import") (part "C-USC0805"))
    )
    (comp (ref "C5")
      (value "0.1uF")
      (footprint "eagle-import:C0603")
      (libsource (lib "eagle-import") (part "adafruit_C-USC0603"))
    )
    (comp (ref "C6")
      (value "0.1uF/12V")
      (footprint "eagle-import:C0805")
      (libsource (lib "eagle-import") (part "C-USC0805"))
    )
    (comp (ref "C7")
      (value "22pF")
      (footprint "eagle-import:C0603")
      (libsource (lib "eagle-import") (part "adafruit_C-USC0603"))
    )
    (comp (ref "C8")
      (value "22pF")
      (footprint "eagle-import:C0603")
      (libsource (lib "eagle-import") (part "adafruit_C-USC0603"))
    )
    (comp (ref "ETH3")
      (value "CVM")
      (footprint "eagle-import:A122645-ND")
      (libsource (lib "eagle-import") (part "ETHERNET"))
    )
    (comp (ref "F3")
      (value "POLYFUSE")
      (footprint "eagle-import:1206")
      (libsource (lib "eagle-import") (part "POLYFUSE"))
    )
    (comp (ref "FRAME3")
      (value "FRAME-LETTERNO_PACKAGE")
      (footprint "eagle-import:DUMMY")
      (fields (field (name "DESIGNER") "Nobody"))
      (libsource (lib "eagle-import") (part "FRAME-LETTERNO_PACKAGE"))
    )
    (comp (ref "ISP1")
      (value "AVRISP-BOX")
      (footprint "eagle-import:AVRISP-BOX")
      (libsource (lib "eagle-import") (part "AVRISP-BOX"))
    )
    (comp (ref "R9")
      (value "10k")
      (footprint "eagle-import:R0603")
      (libsource (lib "eagle-import") (part "R-US_R0603"))
    )
    (comp (ref "R10")
      (value "10k")
      (footprint "eagle-import:0805")
      (libsource (lib "eagle-import") (part "RESISTOR0805-RES"))
    )
    (comp (ref "R11")
      (value "10k")
      (footprint "eagle-import:0805")
      (libsource (lib "eagle-import") (part "RESISTOR0805-RES"))
    )
    (comp (ref "R12")
      (value "10k")
      (footprint "eagle-import:0805")
      (libsource (lib "eagle-import") (part "RESISTOR0805-RES"))
    )
    (comp (ref "R13")
      (value "10k")
      (footprint "eagle-import:0805")
      (libsource (lib "eagle-import") (part "RESISTOR0805-RES"))
    )
    (comp (ref "S1")
      (value "EG4621CT-ND")
      (footprint "eagle-import:EG4621CT-ND")
      (libsource (lib "eagle-import") (part "EG4621CT-ND"))
    )
    (comp (ref "U2")
      (value "MAX3221CPWR")
      (footprint "eagle-import:SOP65P640X120-16N")
      (libsource (lib "eagle-import") (part "MAX3221CPWR"))
    )
    (comp (ref "U3")
      (value "ATMEGA328P_TQFP")
      (footprint "eagle-import:TQFP32-08")
      (libsource (lib "eagle-import") (part "ATMEGA328P_TQFP"))
    )
    (comp (ref "Y1")
      (value "CRYSTALHC49US")
      (footprint "eagle-import:HC49US")
      (libsource (lib "eagle-import") (part "CRYSTALHC49US"))
    )
  )
  (nets
    (net (code "1") (name "+3.3V") (class "Default")
      (node (ref "C10") (pin "1") (pinfunction "1_1") (pintype "passive"))
      (node (ref "C19") (pin "1") (pinfunction "1_1") (pintype "passive"))
      (node (ref "C2") (pin "1") (pinfunction "1_1") (pintype "passive"))
      (node (ref "C20") (pin "1") (pinfunction "1_1") (pintype "passive"))
      (node (ref "C5") (pin "1") (pinfunction "1_1") (pintype "passive"))
      (node (ref "C9") (pin "1") (pinfunction "1_1") (pintype "passive"))
      (node (ref "D1") (pin "C") (pinfunction "C_C") (pintype "passive"))
      (node (ref "F1") (pin "2") (pinfunction "2_2") (pintype "passive"))
      (node (ref "LCD1") (pin "V") (pinfunction "V_V") (pintype "bidirectional"))
      (node (ref "R14") (pin "2") (pinfunction "2_2") (pintype "passive"))
      (node (ref "R22") (pin "2") (pinfunction "2_2") (pintype "passive"))
      (node (ref "R3") (pin "1") (pinfunction "1_1") (pintype "passive"))
      (node (ref "R4") (pin "1") (pinfunction "1_1") (pintype "passive"))
      (node (ref "R5") (pin "2") (pinfunction "2_2") (pintype "passive"))
      (node (ref "R6") (pin "2") (pinfunction "2_2") (pintype "passive"))
      (node (ref "R9") (pin "2") (pinfunction "2_2") (pintype "passive"))
      (node (ref "RTC1") (pin "P$1") (pinfunction "3.3V_P$1") (pintype "bidirectional"))
      (node (ref "SHT1") (pin "VIN") (pinfunction "VCC_VIN") (pintype "bidirectional"))
      (node (ref "SJ2") (pin "1") (pinfunction "1_1") (pintype "passive"))
      (node (ref "U2") (pin "15") (pinfunction "VCC_15") (pintype "power_in"))
      (node (ref "U2") (pin "16") (pinfunction "~{FORCEOFF}_16") (pintype "input"))
      (node (ref "U3") (pin "18") (pinfunction "AVCC_18") (pintype "bidirectional"))
      (node (ref "U3") (pin "20") (pinfunction "AREF_20") (pintype "bidirectional"))
      (node (ref "U3") (pin "4") (pinfunction "VCC_4") (pintype "bidirectional"))
      (node (ref "U3") (pin "6") (pinfunction "VCC_6") (pintype "bidirectional"))
      (node (ref "U4") (pin "18") (pinfunction "AVCC_18") (pintype "bidirectional"))
      (node (ref "U4") (pin "20") (pinfunction "AREF_20") (pintype "bidirectional"))
      (node (ref "U4") (pin "4") (pinfunction "VCC_4") (pintype "bidirectional"))
      (node (ref "U4") (pin "6") (pinfunction "VCC_6") (pintype "bidirectional"))
      (node (ref "U5") (pin "15") (pinfunction "VCC_15") (pintype "power_in"))
      (node (ref "U5") (pin "16") (pinfunction "~{FORCEOFF}_16") (pintype "input"))
      (node (ref "U6") (pin "18") (pinfunction "AVCC_18") (pintype "bidirectional"))
      (node (ref "U6") (pin "20") (pinfunction "AREF_20") (pintype "bidirectional"))
      (node (ref "U6") (pin "4") (pinfunction "VCC_4") (pintype "bidirectional"))
      (node (ref "U6") (pin "6") (pinfunction "VCC_6") (pintype "bidirectional"))
    )
    (net (code "2") (name "AREF") (class "Default")
      (node (ref "T1") (pin "AREF") (pinfunction "AREF_AREF") (pintype "power_in"))
    )
    (net (code "3") (name "ATMEG1_RESET") (class "Default")
      (node (ref "ISP1") (pin "5") (pinfunction "RST_5") (pintype "output"))
      (node (ref "R9") (pin "1") (pinfunction "1_1") (pintype "passive"))
      (node (ref "S1") (pin "P$3") (pinfunction "P$2_P$3") (pintype "bidirectional"))
      (node (ref "S1") (pin "P$4") (pinfunction "P$2_P$4") (pintype "bidirectional"))
      (node (ref "U3") (pin "29") (pinfunction "PC6(/RESET)_29") (pintype "bidirectional"))
    )
    (net (code "4") (name "ATMEG2_RESET") (class "Default")
      (node (ref "ISP2") (pin "5") (pinfunction "RST_5") (pintype "output"))
      (node (ref "R14") (pin "1") (pinfunction "1_1") (pintype "passive"))
      (node (ref "S2") (pin "P$3") (pinfunction "P$2_P$3") (pintype "bidirectional"))
      (node (ref "S2") (pin "P$4") (pinfunction "P$2_P$4") (pintype "bidirectional"))
      (node (ref "U4") (pin "29") (pinfunction "PC6(/RESET)_29") (pintype "bidirectional"))
    )
    (net (code "5") (name "ATMEG3_RESET") (class "Default")
      (node (ref "ISP3") (pin "5") (pinfunction "RST_5") (pintype "output"))
      (node (ref "R22") (pin "1") (pinfunction "1_1") (pintype "passive"))
      (node (ref "U6") (pin "29") (pinfunction "PC6(/RESET)_29") (pintype "bidirectional"))
    )
    (net (code "6") (name "AUX5") (class "Default")
      (node (ref "C17") (pin "+") (pinfunction "+_+") (pintype "passive"))
      (node (ref "C21") (pin "+") (pinfunction "+_+") (pintype "passive"))
      (node (ref "C22") (pin "1") (pinfunction "1_1") (pintype "passive"))
      (node (ref "C23") (pin "1") (pinfunction "1_1") (pintype "passive"))
      (node (ref "CAN1") (pin "5V") (pinfunction "+5V_5V") (pintype "bidirectional"))
      (node (ref "CAN1") (pin "VCC") (pinfunction "VCC_VCC") (pintype "bidirectional"))
      (node (ref "D3") (pin "P$1") (pinfunction "P$1_P$1") (pintype "bidirectional"))
      (node (ref "E1") (pin "3") (pinfunction "3_3") (pintype "bidirectional"))
      (node (ref "E1") (pin "4") (pinfunction "4_4") (pintype "bidirectional"))
      (node (ref "F10") (pin "1") (pinfunction "1_1") (pintype "passive"))
    )
    (net (code "7") (name "AUX12") (class "Default")
      (node (ref "ETH1") (pin "P$5") (pinfunction "5_P$5") (pintype "bidirectional"))
      (node (ref "ETH6") (pin "P$1") (pinfunction "1_P$1") (pintype "bidirectional"))
      (node (ref "F4") (pin "1") (pinfunction "1_1") (pintype "passive"))
      (node (ref "F9") (pin "1") (pinfunction "1_1") (pintype "passive"))
    )
    (net (code "8") (name "CAPCURR") (class "Default")
      (node (ref "ETH2") (pin "P$1") (pinfunction "1_P$1") (pintype "bidirectional"))
      (node (ref "R5") (pin "1") (pinfunction "1_1") (pintype "passive"))
      (node (ref "T1") (pin "17/A3") (pinfunction "17/A3/T_17/A3") (pintype "bidirectional"))
    )
    (net (code "9") (name "CAPVOLT") (class "Default")
      (node (ref "ETH2") (pin "P$3") (pinfunction "3_P$3") (pintype "bidirectional"))
      (node (ref "R7") (pin "1") (pinfunction "1_1") (pintype "passive"))
      (node (ref "T1") (pin "14/A0") (pinfunction "14/A0_14/A0") (pintype "bidirectional"))
    )
    (net (code "10") (name "CAP_R") (class "Default")
      (node (ref "IC1") (pin "8") (pinfunction "I0_8") (pintype "input"))
      (node (ref "T1") (pin "11") (pinfunction "11/MOSI_11") (pintype "bidirectional"))
    )
    (net (code "11") (name "CAP_R_OUT") (class "Default")
      (node (ref "ETH1") (pin "P$3") (pinfunction "3_P$3") (pintype "bidirectional"))
      (node (ref "IC1") (pin "10") (pinfunction "O_10") (pintype "output"))
    )
    (net (code "12") (name "CHARGE_R") (class "Default")
      (node (ref "IC1") (pin "12") (pinfunction "I0_12") (pintype "input"))
      (node (ref "T1") (pin "12") (pinfunction "12/MISO_12") (pintype "bidirectional"))
    )
    (net (code "13") (name "CHARGE_R_OUT") (class "Default")
      (node (ref "ETH1") (pin "P$4") (pinfunction "4_P$4") (pintype "bidirectional"))
      (node (ref "IC1") (pin "11") (pinfunction "O_11") (pintype "output"))
    )
    (net (code "14") (name "CVMRX") (class "Default")
      (node (ref "U2") (pin "9") (pinfunction "ROUT_9") (pintype "output"))
      (node (ref "U3") (pin "30") (pinfunction "PD0(RXD)_30") (pintype "bidirectional"))
    )
    (net (code "15") (name "CVMRX12") (class "Default")
      (node (ref "ETH3") (pin "P$3") (pinfunction "3_P$3") (pintype "bidirectional"))
      (node (ref "U2") (pin "8") (pinfunction "RIN_8") (pintype "input"))
    )
    (net (code "16") (name "CVMSIG1") (class "Default")
      (node (ref "ETH3") (pin "P$5") (pinfunction "5_P$5") (pintype "bidirectional"))
      (node (ref "R13") (pin "2") (pinfunction "2_2") (pintype "passive"))
      (node (ref "U1") (pin "6") (pinfunction "1C0_6") (pintype "input"))
    )
    (net (code "17") (name "CVMSIG2") (class "Default")
      (node (ref "ETH3") (pin "P$6") (pinfunction "6_P$6") (pintype "bidirectional"))
      (node (ref "R12") (pin "2") (pinfunction "2_2") (pintype "passive"))
      (node (ref "U1") (pin "5") (pinfunction "1C1_5") (pintype "input"))
    )
    (net (code "18") (name "CVMSIG3") (class "Default")
      (node (ref "ETH3") (pin "P$7") (pinfunction "7_P$7") (pintype "bidirectional"))
      (node (ref "R11") (pin "2") (pinfunction "2_2") (pintype "passive"))
      (node (ref "U1") (pin "4") (pinfunction "1C2_4") (pintype "input"))
    )
    (net (code "19") (name "CVMSIG4") (class "Default")
      (node (ref "ETH3") (pin "P$8") (pinfunction "8_P$8") (pintype "bidirectional"))
      (node (ref "R10") (pin "2") (pinfunction "2_2") (pintype "passive"))
      (node (ref "U1") (pin "3") (pinfunction "1C3_3") (pintype "input"))
    )
    (net (code "20") (name "CVMTX") (class "Default")
      (node (ref "U2") (pin "11") (pinfunction "DIN_11") (pintype "input"))
      (node (ref "U3") (pin "31") (pinfunction "PD1(TXD)_31") (pintype "bidirectional"))
    )
    (net (code "21") (name "CVMTX12") (class "Default")
      (node (ref "ETH3") (pin "P$2") (pinfunction "2_P$2") (pintype "bidirectional"))
      (node (ref "U2") (pin "13") (pinfunction "DOUT_13") (pintype "output"))
    )
    (net (code "22") (name "CVM_SER_INVALID") (class "Default")
      (node (ref "U2") (pin "10") (pinfunction "~{INVALID}_10") (pintype "output"))
      (node (ref "U3") (pin "1") (pinfunction "PD3(INT1)_1") (pintype "bidirectional"))
    )
    (net (code "23") (name "EXTRA_SIG") (class "Default")
      (node (ref "ETH7") (pin "P$2") (pinfunction "2_P$2") (pintype "bidirectional"))
      (node (ref "R21") (pin "2") (pinfunction "2_2") (pintype "passive"))
      (node (ref "U1") (pin "11") (pinfunction "2C1_11") (pintype "input"))
    )
    (net (code "24") (name "EXTRA_V") (class "Default")
      (node (ref "M1") (pin "IN3") (pinfunction "IN3_IN3") (pintype "bidirectional"))
      (node (ref "T1") (pin "10") (pinfunction "10/TX2/PWM_10") (pintype "bidirectional"))
    )
    (net (code "25") (name "EXTRA_V_G") (class "Default")
      (node (ref "ETH6") (pin "P$6") (pinfunction "6_P$6") (pintype "bidirectional"))
      (node (ref "M1") (pin "OUT3") (pinfunction "OUT3_OUT3") (pintype "bidirectional"))
      (node (ref "R15") (pin "2") (pinfunction "2_2") (pintype "passive"))
    )
    (net (code "26") (name "FC5") (class "Default")
      (node (ref "C18") (pin "+") (pinfunction "+_+") (pintype "passive"))
      (node (ref "C24") (pin "1") (pinfunction "1_1") (pintype "passive"))
      (node (ref "C25") (pin "+") (pinfunction "+_+") (pintype "passive"))
      (node (ref "C26") (pin "1") (pinfunction "1_1") (pintype "passive"))
      (node (ref "D2") (pin "P$1") (pinfunction "P$1_P$1") (pintype "bidirectional"))
      (node (ref "ETH2") (pin "P$5") (pinfunction "5_P$5") (pintype "bidirectional"))
      (node (ref "F2") (pin "2") (pinfunction "2_2") (pintype "passive"))
      (node (ref "F3") (pin "1") (pinfunction "1_1") (pintype "passive"))
      (node (ref "F6") (pin "1") (pinfunction "1_1") (pintype "passive"))
      (node (ref "F7") (pin "1") (pinfunction "1_1") (pintype "passive"))
      (node (ref "M1") (pin "VDD") (pinfunction "V+_VDD") (pintype "bidirectional"))
      (node (ref "O1") (pin "P$4") (pinfunction "RAW_P$4") (pintype "bidirectional"))
      (node (ref "U1") (pin "16") (pinfunction "VCC_16") (pintype "power_in"))
    )
    (net (code "27") (name "FC12") (class "Default")
      (node (ref "ETH1") (pin "P$6") (pinfunction "6_P$6") (pintype "bidirectional"))
      (node (ref "ETH5") (pin "P$1") (pinfunction "1_P$1") (pintype "bidirectional"))
      (node (ref "ETH6") (pin "P$3") (pinfunction "3_P$3") (pintype "bidirectional"))
      (node (ref "ETH6") (pin "P$5") (pinfunction "5_P$5") (pintype "bidirectional"))
      (node (ref "F5") (pin "1") (pinfunction "1_1") (pintype "passive"))
      (node (ref "F8") (pin "1") (pinfunction "1_1") (pintype "passive"))
    )
    (net (code "28") (name "FCCURR") (class "Default")
      (node (ref "ETH2") (pin "P$2") (pinfunction "2_P$2") (pintype "bidirectional"))
      (node (ref "R6") (pin "1") (pinfunction "1_1") (pintype "passive"))
      (node (ref "T1") (pin "15/A1") (pinfunction "15/A1/T_15/A1") (pintype "bidirectional"))
    )
    (net (code "29") (name "FCC_R") (class "Default")
      (node (ref "ETH2") (pin "P$6") (pinfunction "6_P$6") (pintype "bidirectional"))
      (node (ref "T1") (pin "20/A6") (pinfunction "20/A6/PWM_20/A6") (pintype "bidirectional"))
    )
    (net (code "30") (name "FCPRES") (class "Default")
      (node (ref "R18") (pin "2") (pinfunction "2_2") (pintype "passive"))
      (node (ref "R19") (pin "2") (pinfunction "2_2") (pintype "passive"))
      (node (ref "T1") (pin "A11") (pinfunction "A11_A11") (pintype "bidirectional"))
    )
    (net (code "31") (name "FCVOLT") (class "Default")
      (node (ref "ETH2") (pin "P$4") (pinfunction "4_P$4") (pintype "bidirectional"))
      (node (ref "R8") (pin "1") (pinfunction "1_1") (pintype "passive"))
      (node (ref "T1") (pin "16/A2") (pinfunction "16/A2/T_16/A2") (pintype "bidirectional"))
    )
    (net (code "32") (name "GND") (class "Default")
      (node (ref "C10") (pin "2") (pinfunction "2_2") (pintype "passive"))
      (node (ref "C11") (pin "2") (pinfunction "2_2") (pintype "passive"))
      (node (ref "C12") (pin "2") (pinfunction "2_2") (pintype "passive"))
      (node (ref "C14") (pin "2") (pinfunction "2_2") (pintype "passive"))
      (node (ref "C15") (pin "2") (pinfunction "2_2") (pintype "passive"))
      (node (ref "C17") (pin "-") (pinfunction "-_-") (pintype "passive"))
      (node (ref "C18") (pin "-") (pinfunction "-_-") (pintype "passive"))
      (node (ref "C19") (pin "2") (pinfunction "2_2") (pintype "passive"))
      (node (ref "C2") (pin "2") (pinfunction "2_2") (pintype "passive"))
      (node (ref "C20") (pin "2") (pinfunction "2_2") (pintype "passive"))
      (node (ref "C21") (pin "-") (pinfunction "-_-") (pintype "passive"))
      (node (ref "C22") (pin "2") (pinfunction "2_2") (pintype "passive"))
      (node (ref "C23") (pin "2") (pinfunction "2_2") (pintype "passive"))
      (node (ref "C24") (pin "2") (pinfunction "2_2") (pintype "passive"))
      (node (ref "C25") (pin "-") (pinfunction "-_-") (pintype "passive"))
      (node (ref "C26") (pin "2") (pinfunction "2_2") (pintype "passive"))
      (node (ref "C3") (pin "2") (pinfunction "2_2") (pintype "passive"))
      (node (ref "C4") (pin "2") (pinfunction "2_2") (pintype "passive"))
      (node (ref "C5") (pin "2") (pinfunction "2_2") (pintype "passive"))
      (node (ref "C7") (pin "2") (pinfunction "2_2") (pintype "passive"))
      (node (ref "C8") (pin "2") (pinfunction "2_2") (pintype "passive"))
      (node (ref "C9") (pin "2") (pinfunction "2_2") (pintype "passive"))
      (node (ref "CAN1") (pin "GND") (pinfunction "GND_GND") (pintype "bidirectional"))
      (node (ref "CAN1") (pin "GND_") (pinfunction "GND__GND_") (pintype "bidirectional"))
      (node (ref "D1") (pin "A") (pinfunction "A_A") (pintype "passive"))
      (node (ref "D2") (pin "P$2") (pinfunction "P$2_P$2") (pintype "bidirectional"))
      (node (ref "D3") (pin "P$2") (pinfunction "P$2_P$2") (pintype "bidirectional"))
      (node (ref "E1") (pin "5") (pinfunction "5_5") (pintype "bidirectional"))
      (node (ref "E1") (pin "6") (pinfunction "6_6") (pintype "bidirectional"))
      (node (ref "E1") (pin "SH1") (pinfunction "SH1_SH1") (pintype "bidirectional"))
      (node (ref "E1") (pin "SH2") (pinfunction "SH2_SH2") (pintype "bidirectional"))
      (node (ref "E2") (pin "5") (pinfunction "5_5") (pintype "bidirectional"))
      (node (ref "E2") (pin "6") (pinfunction "6_6") (pintype "bidirectional"))
      (node (ref "E2") (pin "SH1") (pinfunction "SH1_SH1") (pintype "bidirectional"))
      (node (ref "E2") (pin "SH2") (pinfunction "SH2_SH2") (pintype "bidirectional"))
      (node (ref "ETH1") (pin "P$13") (pinfunction "SHD1_P$13") (pintype "bidirectional"))
      (node (ref "ETH1") (pin "P$14") (pinfunction "SHD2_P$14") (pintype "bidirectional"))
      (node (ref "ETH1") (pin "P$7") (pinfunction "7_P$7") (pintype "bidirectional"))
      (node (ref "ETH1") (pin "P$8") (pinfunction "8_P$8") (pintype "bidirectional"))
      (node (ref "ETH2") (pin "P$13") (pinfunction "SHD1_P$13") (pintype "bidirectional"))
      (node (ref "ETH2") (pin "P$14") (pinfunction "SHD2_P$14") (pintype "bidirectional"))
      (node (ref "ETH2") (pin "P$7") (pinfunction "7_P$7") (pintype "bidirectional"))
      (node (ref "ETH2") (pin "P$8") (pinfunction "8_P$8") (pintype "bidirectional"))
      (node (ref "ETH3") (pin "P$13") (pinfunction "SHD1_P$13") (pintype "bidirectional"))
      (node (ref "ETH3") (pin "P$14") (pinfunction "SHD2_P$14") (pintype "bidirectional"))
      (node (ref "ETH3") (pin "P$4") (pinfunction "4_P$4") (pintype "bidirectional"))
      (node (ref "ETH4") (pin "P$13") (pinfunction "SHD1_P$13") (pintype "bidirectional"))
      (node (ref "ETH4") (pin "P$14") (pinfunction "SHD2_P$14") (pintype "bidirectional"))
      (node (ref "ETH4") (pin "P$8") (pinfunction "8_P$8") (pintype "bidirectional"))
      (node (ref "ETH5") (pin "P$13") (pinfunction "SHD1_P$13") (pintype "bidirectional"))
      (node (ref "ETH5") (pin "P$14") (pinfunction "SHD2_P$14") (pintype "bidirectional"))
      (node (ref "ETH5") (pin "P$2") (pinfunction "2_P$2") (pintype "bidirectional"))
      (node (ref "ETH6") (pin "P$13") (pinfunction "SHD1_P$13") (pintype "bidirectional"))
      (node (ref "ETH6") (pin "P$14") (pinfunction "SHD2_P$14") (pintype "bidirectional"))
      (node (ref "ETH7") (pin "P$13") (pinfunction "SHD1_P$13") (pintype "bidirectional"))
      (node (ref "ETH7") (pin "P$14") (pinfunction "SHD2_P$14") (pintype "bidirectional"))
      (node (ref "ETH7") (pin "P$5") (pinfunction "5_P$5") (pintype "bidirectional"))
      (node (ref "FAN1") (pin "GND") (pinfunction "GND_GND") (pintype "bidirectional"))
      (node (ref "FAN1") (pin "GND2") (pinfunction "GND_GND2") (pintype "bidirectional"))
      (node (ref "FAN1") (pin "GND3") (pinfunction "GND_GND3") (pintype "bidirectional"))
      (node (ref "ISP1") (pin "6") (pinfunction "GND_6") (pintype "power_in"))
      (node (ref "ISP2") (pin "6") (pinfunction "GND_6") (pintype "power_in"))
      (node (ref "ISP3") (pin "6") (pinfunction "GND_6") (pintype "power_in"))
      (node (ref "LCD1") (pin "GND1") (pinfunction "GND_GND1") (pintype "bidirectional"))
      (node (ref "LCD1") (pin "GND10") (pinfunction "GND_GND10") (pintype "bidirectional"))
      (node (ref "LCD1") (pin "GND11") (pinfunction "GND_GND11") (pintype "bidirectional"))
      (node (ref "LCD1") (pin "GND12") (pinfunction "GND_GND12") (pintype "bidirectional"))
      (node (ref "LCD1") (pin "GND13") (pinfunction "GND_GND13") (pintype "bidirectional"))
      (node (ref "LCD1") (pin "GND2") (pinfunction "GND_GND2") (pintype "bidirectional"))
      (node (ref "LCD1") (pin "GND3") (pinfunction "GND_GND3") (pintype "bidirectional"))
      (node (ref "LCD1") (pin "GND4") (pinfunction "GND_GND4") (pintype "bidirectional"))
      (node (ref "LCD1") (pin "GND5") (pinfunction "GND_GND5") (pintype "bidirectional"))
      (node (ref "LCD1") (pin "GND6") (pinfunction "GND_GND6") (pintype "bidirectional"))
      (node (ref "LCD1") (pin "GND7") (pinfunction "GND_GND7") (pintype "bidirectional"))
      (node (ref "LCD1") (pin "GND8") (pinfunction "GND_GND8") (pintype "bidirectional"))
      (node (ref "LCD1") (pin "GND9") (pinfunction "GND_GND9") (pintype "bidirectional"))
      (node (ref "LED1") (pin "C") (pinfunction "C_C") (pintype "passive"))
      (node (ref "LED10") (pin "C") (pinfunction "C_C") (pintype "passive"))
      (node (ref "LED11") (pin "C") (pinfunction "C_C") (pintype "passive"))
      (node (ref "LED12") (pin "C") (pinfunction "C_C") (pintype "passive"))
      (node (ref "LED2") (pin "C") (pinfunction "C_C") (pintype "passive"))
      (node (ref "LED3") (pin "C") (pinfunction "C_C") (pintype "passive"))
      (node (ref "LED4") (pin "C") (pinfunction "C_C") (pintype "passive"))
      (node (ref "LED5") (pin "C") (pinfunction "C_C") (pintype "passive"))
      (node (ref "LED6") (pin "C") (pinfunction "C_C") (pintype "passive"))
      (node (ref "LED7") (pin "C") (pinfunction "C_C") (pintype "passive"))
      (node (ref "LED8") (pin "C") (pinfunction "C_C") (pintype "passive"))
      (node (ref "LED9") (pin "C") (pinfunction "C_C") (pintype "passive"))
      (node (ref "M1") (pin "GND") (pinfunction "GND_GND") (pintype "bidirectional"))
      (node (ref "M1") (pin "GND1") (pinfunction "GND_GND1") (pintype "bidirectional"))
      (node (ref "M1") (pin "GND2") (pinfunction "GND_GND2") (pintype "bidirectional"))
      (node (ref "M1") (pin "VSS") (pinfunction "GND_VSS") (pintype "bidirectional"))
      (node (ref "O1") (pin "P$5") (pinfunction "GND_P$5") (pintype "bidirectional"))
      (node (ref "O1") (pin "P$6") (pinfunction "GND2_P$6") (pintype "bidirectional"))
      (node (ref "R1") (pin "2") (pinfunction "2_2") (pintype "passive"))
      (node (ref "R10") (pin "1") (pinfunction "1_1") (pintype "passive"))
      (node (ref "R11") (pin "1") (pinfunction "1_1") (pintype "passive"))
      (node (ref "R12") (pin "1") (pinfunction "1_1") (pintype "passive"))
      (node (ref "R13") (pin "1") (pinfunction "1_1") (pintype "passive"))
      (node (ref "R15") (pin "1") (pinfunction "1_1") (pintype "passive"))
      (node (ref "R16") (pin "1") (pinfunction "1_1") (pintype "passive"))
      (node (ref "R17") (pin "1") (pinfunction "1_1") (pintype "passive"))
      (node (ref "R18") (pin "1") (pinfunction "1_1") (pintype "passive"))
      (node (ref "R2") (pin "1") (pinfunction "1_1") (pintype "passive"))
      (node (ref "R20") (pin "1") (pinfunction "1_1") (pintype "passive"))
      (node (ref "R21") (pin "1") (pinfunction "1_1") (pintype "passive"))
      (node (ref "R7") (pin "2") (pinfunction "2_2") (pintype "passive"))
      (node (ref "R8") (pin "2") (pinfunction "2_2") (pintype "passive"))
      (node (ref "RTC1") (pin "P$2") (pinfunction "GND_P$2") (pintype "bidirectional"))
      (node (ref "S1") (pin "P$1") (pinfunction "P$1_P$1") (pintype "bidirectional"))
      (node (ref "S1") (pin "P$2") (pinfunction "P$1_P$2") (pintype "bidirectional"))
      (node (ref "S2") (pin "P$1") (pinfunction "P$1_P$1") (pintype "bidirectional"))
      (node (ref "S2") (pin "P$2") (pinfunction "P$1_P$2") (pintype "bidirectional"))
      (node (ref "SHT1") (pin "GND") (pinfunction "GND_GND") (pintype "bidirectional"))
      (node (ref "SJ1") (pin "1") (pinfunction "1_1") (pintype "passive"))
      (node (ref "T1") (pin "AGND") (pinfunction "AGND_AGND") (pintype "power_in"))
      (node (ref "T1") (pin "GND") (pinfunction "GND_GND") (pintype "power_in"))
      (node (ref "T1") (pin "GND1") (pinfunction "GND_GND1") (pintype "power_in"))
      (node (ref "U1") (pin "1") (pinfunction "1~{G}_1") (pintype "input"))
      (node (ref "U1") (pin "15") (pinfunction "2~{G}_15") (pintype "input"))
      (node (ref "U1") (pin "8") (pinfunction "GND_8") (pintype "passive"))
      (node (ref "U2") (pin "1") (pinfunction "~{EN}_1") (pintype "input"))
      (node (ref "U2") (pin "12") (pinfunction "FORCEON_12") (pintype "input"))
      (node (ref "U2") (pin "14") (pinfunction "GND_14") (pintype "passive"))
      (node (ref "U3") (pin "21") (pinfunction "AGND_21") (pintype "bidirectional"))
      (node (ref "U3") (pin "3") (pinfunction "GND_3") (pintype "bidirectional"))
      (node (ref "U3") (pin "5") (pinfunction "GND_5") (pintype "bidirectional"))
      (node (ref "U4") (pin "21") (pinfunction "AGND_21") (pintype "bidirectional"))
      (node (ref "U4") (pin "3") (pinfunction "GND_3") (pintype "bidirectional"))
      (node (ref "U4") (pin "5") (pinfunction "GND_5") (pintype "bidirectional"))
      (node (ref "U5") (pin "1") (pinfunction "~{EN}_1") (pintype "input"))
      (node (ref "U5") (pin "12") (pinfunction "FORCEON_12") (pintype "input"))
      (node (ref "U5") (pin "14") (pinfunction "GND_14") (pintype "passive"))
      (node (ref "U6") (pin "21") (pinfunction "AGND_21") (pintype "bidirectional"))
      (node (ref "U6") (pin "3") (pinfunction "GND_3") (pintype "bidirectional"))
      (node (ref "U6") (pin "5") (pinfunction "GND_5") (pintype "bidirectional"))
    )
    (net (code "33") (name "H2_OK") (class "Default")
      (node (ref "ETH7") (pin "P$1") (pinfunction "1_P$1") (pintype "bidirectional"))
      (node (ref "IC1") (pin "13") (pinfunction "I1_13") (pintype "input"))
      (node (ref "IC1") (pin "2") (pinfunction "I1_2") (pintype "input"))
      (node (ref "IC1") (pin "6") (pinfunction "I1_6") (pintype "input"))
      (node (ref "IC1") (pin "9") (pinfunction "I1_9") (pintype "input"))
      (node (ref "M1") (pin "ESTOP") (pinfunction "ESTOP_ESTOP") (pintype "bidirectional"))
      (node (ref "R20") (pin "2") (pinfunction "2_2") (pintype "passive"))
      (node (ref "U1") (pin "10") (pinfunction "2C0_10") (pintype "input"))
    )
    (net (code "34") (name "MISO1") (class "Default")
      (node (ref "ISP1") (pin "1") (pinfunction "MISO_1") (pintype "input"))
      (node (ref "U3") (pin "16") (pinfunction "PB4(MISO)_16") (pintype "bidirectional"))
    )
    (net (code "35") (name "MISO2") (class "Default")
      (node (ref "ISP2") (pin "1") (pinfunction "MISO_1") (pintype "input"))
      (node (ref "U4") (pin "16") (pinfunction "PB4(MISO)_16") (pintype "bidirectional"))
    )
    (net (code "36") (name "MISO3") (class "Default")
      (node (ref "ISP3") (pin "1") (pinfunction "MISO_1") (pintype "input"))
      (node (ref "U6") (pin "16") (pinfunction "PB4(MISO)_16") (pintype "bidirectional"))
    )
    (net (code "37") (name "MOSI1") (class "Default")
      (node (ref "ISP1") (pin "4") (pinfunction "MOSI_4") (pintype "output"))
      (node (ref "U3") (pin "15") (pinfunction "PB3(MOSI/OC2)_15") (pintype "bidirectional"))
    )
    (net (code "38") (name "MOSI2") (class "Default")
      (node (ref "ISP2") (pin "4") (pinfunction "MOSI_4") (pintype "output"))
      (node (ref "U4") (pin "15") (pinfunction "PB3(MOSI/OC2)_15") (pintype "bidirectional"))
    )
    (net (code "39") (name "MOSI3") (class "Default")
      (node (ref "ISP3") (pin "4") (pinfunction "MOSI_4") (pintype "output"))
      (node (ref "U6") (pin "15") (pinfunction "PB3(MOSI/OC2)_15") (pintype "bidirectional"))
    )
    (net (code "40") (name "MOTOR_R") (class "Default")
      (node (ref "IC1") (pin "5") (pinfunction "I0_5") (pintype "input"))
      (node (ref "T1") (pin "22/A8") (pinfunction "22/A8/T/PWM_22/A8") (pintype "bidirectional"))
    )
    (net (code "41") (name "MOTOR_R_OUT") (class "Default")
      (node (ref "ETH1") (pin "P$2") (pinfunction "2_P$2") (pintype "bidirectional"))
      (node (ref "IC1") (pin "4") (pinfunction "O_4") (pintype "output"))
    )
    (net (code "42") (name "MRX") (class "Default")
      (node (ref "U4") (pin "30") (pinfunction "PD0(RXD)_30") (pintype "bidirectional"))
      (node (ref "U5") (pin "9") (pinfunction "ROUT_9") (pintype "output"))
    )
    (net (code "43") (name "MRX12") (class "Default")
      (node (ref "ETH4") (pin "P$2") (pinfunction "2_P$2") (pintype "bidirectional"))
      (node (ref "U5") (pin "8") (pinfunction "RIN_8") (pintype "input"))
    )
    (net (code "44") (name "MTX") (class "Default")
      (node (ref "U4") (pin "31") (pinfunction "PD1(TXD)_31") (pintype "bidirectional"))
      (node (ref "U5") (pin "11") (pinfunction "DIN_11") (pintype "input"))
    )
    (net (code "45") (name "MTX12") (class "Default")
      (node (ref "ETH4") (pin "P$1") (pinfunction "1_P$1") (pintype "bidirectional"))
      (node (ref "U5") (pin "13") (pinfunction "DOUT_13") (pintype "output"))
    )
    (net (code "46") (name "MULTA") (class "Default")
      (node (ref "T1") (pin "3") (pinfunction "3/CAN-TX/PWM_3") (pintype "bidirectional"))
      (node (ref "U1") (pin "14") (pinfunction "A_14") (pintype "input"))
    )
    (net (code "47") (name "MULTB") (class "Default")
      (node (ref "T1") (pin "4") (pinfunction "4/CAN-RX-PWM_4") (pintype "bidirectional"))
      (node (ref "U1") (pin "2") (pinfunction "B_2") (pintype "input"))
    )
    (net (code "48") (name "MULTO1") (class "Default")
      (node (ref "R1") (pin "1") (pinfunction "1_1") (pintype "passive"))
      (node (ref "T1") (pin "5") (pinfunction "5/PWM_5") (pintype "bidirectional"))
      (node (ref "U1") (pin "7") (pinfunction "1Y_7") (pintype "output"))
    )
    (net (code "49") (name "MULTO2") (class "Default")
      (node (ref "R2") (pin "2") (pinfunction "2_2") (pintype "passive"))
      (node (ref "T1") (pin "2") (pinfunction "2_2") (pintype "bidirectional"))
      (node (ref "U1") (pin "9") (pinfunction "2Y_9") (pintype "output"))
    )
    (net (code "50") (name "M_SER_INVALID") (class "Default")
      (node (ref "U4") (pin "1") (pinfunction "PD3(INT1)_1") (pintype "bidirectional"))
      (node (ref "U5") (pin "10") (pinfunction "~{INVALID}_10") (pintype "output"))
    )
    (net (code "51") (name "M_SIG_1") (class "Default")
      (node (ref "ETH4") (pin "P$6") (pinfunction "6_P$6") (pintype "bidirectional"))
      (node (ref "U1") (pin "12") (pinfunction "2C2_12") (pintype "input"))
    )
    (net (code "52") (name "M_SIG_2") (class "Default")
      (node (ref "ETH4") (pin "P$7") (pinfunction "7_P$7") (pintype "bidirectional"))
      (node (ref "U1") (pin "13") (pinfunction "2C3_13") (pintype "input"))
    )
    (net (code "53") (name "Net-(E1-Pad1)") (class "Default")
      (node (ref "E1") (pin "1") (pinfunction "1_1") (pintype "bidirectional"))
      (node (ref "E1") (pin "2") (pinfunction "2_2") (pintype "bidirectional"))
      (node (ref "F4") (pin "2") (pinfunction "2_2") (pintype "passive"))
    )
    (net (code "54") (name "Net-(E2-Pad1)") (class "Default")
      (node (ref "E2") (pin "1") (pinfunction "1_1") (pintype "bidirectional"))
      (node (ref "E2") (pin "2") (pinfunction "2_2") (pintype "bidirectional"))
      (node (ref "F5") (pin "2") (pinfunction "2_2") (pintype "passive"))
    )
    (net (code "55") (name "Net-(E2-Pad3)") (class "Default")
      (node (ref "E2") (pin "3") (pinfunction "3_3") (pintype "bidirectional"))
      (node (ref "E2") (pin "4") (pinfunction "4_4") (pintype "bidirectional"))
      (node (ref "F6") (pin "2") (pinfunction "2_2") (pintype "passive"))
    )
    (net (code "56") (name "Net-(ETH3-1)") (class "Default")
      (node (ref "ETH3") (pin "P$1") (pinfunction "1_P$1") (pintype "bidirectional"))
      (node (ref "F3") (pin "2") (pinfunction "2_2") (pintype "passive"))
    )
    (net (code "57") (name "Net-(ETH5-3)") (class "Default")
      (node (ref "ETH5") (pin "P$3") (pinfunction "3_P$3") (pintype "bidirectional"))
      (node (ref "R19") (pin "1") (pinfunction "1_1") (pintype "passive"))
    )
    (net (code "58") (name "Net-(ETH7-6)") (class "Default")
      (node (ref "ETH7") (pin "P$6") (pinfunction "6_P$6") (pintype "bidirectional"))
      (node (ref "F9") (pin "2") (pinfunction "2_2") (pintype "passive"))
    )
    (net (code "59") (name "Net-(ETH7-8)") (class "Default")
      (node (ref "ETH7") (pin "P$8") (pinfunction "8_P$8") (pintype "bidirectional"))
      (node (ref "F10") (pin "2") (pinfunction "2_2") (pintype "passive"))
    )
    (net (code "60") (name "Net-(F1-Pad1)") (class "Default")
      (node (ref "F1") (pin "1") (pinfunction "1_1") (pintype "passive"))
      (node (ref "T1") (pin "3.3V") (pinfunction "3.3V_3.3V") (pintype "power_in"))
      (node (ref "T1") (pin "3.3V1") (pinfunction "3.3V_3.3V1") (pintype "power_in"))
    )
    (net (code "61") (name "Net-(F2-Pad1)") (class "Default")
      (node (ref "F2") (pin "1") (pinfunction "1_1") (pintype "passive"))
      (node (ref "T1") (pin "VIN") (pinfunction "VIN_VIN") (pintype "power_in"))
    )
    (net (code "62") (name "Net-(F7-Pad2)") (class "Default")
      (node (ref "F7") (pin "2") (pinfunction "2_2") (pintype "passive"))
      (node (ref "FAN1") (pin "5") (pinfunction "5V_5") (pintype "bidirectional"))
      (node (ref "FAN1") (pin "5_2") (pinfunction "5V_5_2") (pintype "bidirectional"))
    )
    (net (code "63") (name "Net-(F8-Pad2)") (class "Default")
      (node (ref "F8") (pin "2") (pinfunction "2_2") (pintype "passive"))
      (node (ref "FAN1") (pin "12") (pinfunction "12V_12") (pintype "bidirectional"))
      (node (ref "FAN1") (pin "12_2") (pinfunction "12V_12_2") (pintype "bidirectional"))
      (node (ref "FAN1") (pin "12_3") (pinfunction "12V_12_3") (pintype "bidirectional"))
    )
    (net (code "64") (name "Net-(LED1-PadA)") (class "Default")
      (node (ref "LED1") (pin "A") (pinfunction "A_A") (pintype "passive"))
      (node (ref "R23") (pin "1") (pinfunction "1_1") (pintype "passive"))
    )
    (net (code "65") (name "Net-(LED2-PadA)") (class "Default")
      (node (ref "LED2") (pin "A") (pinfunction "A_A") (pintype "passive"))
      (node (ref "R24") (pin "1") (pinfunction "1_1") (pintype "passive"))
    )
    (net (code "66") (name "Net-(LED3-PadA)") (class "Default")
      (node (ref "LED3") (pin "A") (pinfunction "A_A") (pintype "passive"))
      (node (ref "R25") (pin "1") (pinfunction "1_1") (pintype "passive"))
    )
    (net (code "67") (name "Net-(LED4-PadA)") (class "Default")
      (node (ref "LED4") (pin "A") (pinfunction "A_A") (pintype "passive"))
      (node (ref "R26") (pin "1") (pinfunction "1_1") (pintype "passive"))
    )
    (net (code "68") (name "Net-(LED5-PadA)") (class "Default")
      (node (ref "LED5") (pin "A") (pinfunction "A_A") (pintype "passive"))
      (node (ref "R27") (pin "1") (pinfunction "1_1") (pintype "passive"))
    )
    (net (code "69") (name "Net-(LED6-PadA)") (class "Default")
      (node (ref "LED6") (pin "A") (pinfunction "A_A") (pintype "passive"))
      (node (ref "R28") (pin "1") (pinfunction "1_1") (pintype "passive"))
    )
    (net (code "70") (name "Net-(LED7-PadA)") (class "Default")
      (node (ref "LED7") (pin "A") (pinfunction "A_A") (pintype "passive"))
      (node (ref "R29") (pin "1") (pinfunction "1_1") (pintype "passive"))
    )
    (net (code "71") (name "Net-(LED8-PadA)") (class "Default")
      (node (ref "LED8") (pin "A") (pinfunction "A_A") (pintype "passive"))
      (node (ref "R30") (pin "1") (pinfunction "1_1") (pintype "passive"))
    )
    (net (code "72") (name "Net-(LED9-PadA)") (class "Default")
      (node (ref "LED9") (pin "A") (pinfunction "A_A") (pintype "passive"))
      (node (ref "R31") (pin "1") (pinfunction "1_1") (pintype "passive"))
    )
    (net (code "73") (name "Net-(LED10-PadA)") (class "Default")
      (node (ref "LED10") (pin "A") (pinfunction "A_A") (pintype "passive"))
      (node (ref "R32") (pin "1") (pinfunction "1_1") (pintype "passive"))
    )
    (net (code "74") (name "Net-(LED11-PadA)") (class "Default")
      (node (ref "LED11") (pin "A") (pinfunction "A_A") (pintype "passive"))
      (node (ref "R33") (pin "1") (pinfunction "1_1") (pintype "passive"))
    )
    (net (code "75") (name "Net-(LED12-PadA)") (class "Default")
      (node (ref "LED12") (pin "A") (pinfunction "A_A") (pintype "passive"))
      (node (ref "R34") (pin "1") (pinfunction "1_1") (pintype "passive"))
    )
    (net (code "76") (name "Net-(U2-C1+)") (class "Default")
      (node (ref "C6") (pin "1") (pinfunction "1_1") (pintype "passive"))
      (node (ref "U2") (pin "2") (pinfunction "C1+_2") (pintype "passive"))
    )
    (net (code "77") (name "Net-(U2-C1-)") (class "Default")
      (node (ref "C6") (pin "2") (pinfunction "2_2") (pintype "passive"))
      (node (ref "U2") (pin "4") (pinfunction "C1-_4") (pintype "passive"))
    )
    (net (code "78") (name "Net-(U2-C2+)") (class "Default")
      (node (ref "C1") (pin "1") (pinfunction "1_1") (pintype "passive"))
      (node (ref "U2") (pin "5") (pinfunction "C2+_5") (pintype "passive"))
    )
    (net (code "79") (name "Net-(U2-C2-)") (class "Default")
      (node (ref "C1") (pin "2") (pinfunction "2_2") (pintype "passive"))
      (node (ref "U2") (pin "6") (pinfunction "C2-_6") (pintype "passive"))
    )
    (net (code "80") (name "Net-(U2-V+)") (class "Default")
      (node (ref "C3") (pin "1") (pinfunction "1_1") (pintype "passive"))
      (node (ref "U2") (pin "3") (pinfunction "V+_3") (pintype "power_in"))
    )
    (net (code "81") (name "Net-(U2-V-)") (class "Default")
      (node (ref "C4") (pin "1") (pinfunction "1_1") (pintype "passive"))
      (node (ref "U2") (pin "7") (pinfunction "V-_7") (pintype "power_in"))
    )
    (net (code "82") (name "Net-(U3-PB6(XTAL1{slash}TOSC1))") (class "Default")
      (node (ref "C7") (pin "1") (pinfunction "1_1") (pintype "passive"))
      (node (ref "U3") (pin "7") (pinfunction "PB6(XTAL1/TOSC1)_7") (pintype "bidirectional"))
      (node (ref "Y1") (pin "2") (pinfunction "2_2") (pintype "passive"))
    )
    (net (code "83") (name "Net-(U3-PB7(XTAL2{slash}TOSC2))") (class "Default")
      (node (ref "C8") (pin "1") (pinfunction "1_1") (pintype "passive"))
      (node (ref "U3") (pin "8") (pinfunction "PB7(XTAL2/TOSC2)_8") (pintype "bidirectional"))
      (node (ref "Y1") (pin "1") (pinfunction "1_1") (pintype "passive"))
    )
    (net (code "84") (name "Net-(U4-PB6(XTAL1{slash}TOSC1))") (class "Default")
      (node (ref "C11") (pin "1") (pinfunction "1_1") (pintype "passive"))
      (node (ref "U4") (pin "7") (pinfunction "PB6(XTAL1/TOSC1)_7") (pintype "bidirectional"))
      (node (ref "Y2") (pin "2") (pinfunction "2_2") (pintype "passive"))
    )
    (net (code "85") (name "Net-(U4-PB7(XTAL2{slash}TOSC2))") (class "Default")
      (node (ref "C12") (pin "1") (pinfunction "1_1") (pintype "passive"))
      (node (ref "U4") (pin "8") (pinfunction "PB7(XTAL2/TOSC2)_8") (pintype "bidirectional"))
      (node (ref "Y2") (pin "1") (pinfunction "1_1") (pintype "passive"))
    )
    (net (code "86") (name "Net-(U5-C1+)") (class "Default")
      (node (ref "C16") (pin "1") (pinfunction "1_1") (pintype "passive"))
      (node (ref "U5") (pin "2") (pinfunction "C1+_2") (pintype "passive"))
    )
    (net (code "87") (name "Net-(U5-C1-)") (class "Default")
      (node (ref "C16") (pin "2") (pinfunction "2_2") (pintype "passive"))
      (node (ref "U5") (pin "4") (pinfunction "C1-_4") (pintype "passive"))
    )
    (net (code "88") (name "Net-(U5-C2+)") (class "Default")
      (node (ref "C13") (pin "1") (pinfunction "1_1") (pintype "passive"))
      (node (ref "U5") (pin "5") (pinfunction "C2+_5") (pintype "passive"))
    )
    (net (code "89") (name "Net-(U5-C2-)") (class "Default")
      (node (ref "C13") (pin "2") (pinfunction "2_2") (pintype "passive"))
      (node (ref "U5") (pin "6") (pinfunction "C2-_6") (pintype "passive"))
    )
    (net (code "90") (name "Net-(U5-V+)") (class "Default")
      (node (ref "C14") (pin "1") (pinfunction "1_1") (pintype "passive"))
      (node (ref "U5") (pin "3") (pinfunction "V+_3") (pintype "power_in"))
    )
    (net (code "91") (name "Net-(U5-V-)") (class "Default")
      (node (ref "C15") (pin "1") (pinfunction "1_1") (pintype "passive"))
      (node (ref "U5") (pin "7") (pinfunction "V-_7") (pintype "power_in"))
    )
    (net (code "92") (name "Net-(U6-ADC6)") (class "Default")
      (node (ref "R27") (pin "2") (pinfunction "2_2") (pintype "passive"))
      (node (ref "U6") (pin "19") (pinfunction "ADC6_19") (pintype "bidirectional"))
    )
    (net (code "93") (name "Net-(U6-ADC7)") (class "Default")
      (node (ref "R28") (pin "2") (pinfunction "2_2") (pintype "passive"))
      (node (ref "U6") (pin "22") (pinfunction "ADC7_22") (pintype "bidirectional"))
    )
    (net (code "94") (name "Net-(U6-PC0(ADC0))") (class "Default")
      (node (ref "R23") (pin "2") (pinfunction "2_2") (pintype "passive"))
      (node (ref "U6") (pin "23") (pinfunction "PC0(ADC0)_23") (pintype "bidirectional"))
    )
    (net (code "95") (name "Net-(U6-PC1(ADC1))") (class "Default")
      (node (ref "R24") (pin "2") (pinfunction "2_2") (pintype "passive"))
      (node (ref "U6") (pin "24") (pinfunction "PC1(ADC1)_24") (pintype "bidirectional"))
    )
    (net (code "96") (name "Net-(U6-PC2(ADC2))") (class "Default")
      (node (ref "R25") (pin "2") (pinfunction "2_2") (pintype "passive"))
      (node (ref "U6") (pin "25") (pinfunction "PC2(ADC2)_25") (pintype "bidirectional"))
    )
    (net (code "97") (name "Net-(U6-PC3(ADC3))") (class "Default")
      (node (ref "R26") (pin "2") (pinfunction "2_2") (pintype "passive"))
      (node (ref "U6") (pin "26") (pinfunction "PC3(ADC3)_26") (pintype "bidirectional"))
    )
    (net (code "98") (name "Net-(U6-PD0(RXD))") (class "Default")
      (node (ref "R29") (pin "2") (pinfunction "2_2") (pintype "passive"))
      (node (ref "U6") (pin "30") (pinfunction "PD0(RXD)_30") (pintype "bidirectional"))
    )
    (net (code "99") (name "Net-(U6-PD1(TXD))") (class "Default")
      (node (ref "R30") (pin "2") (pinfunction "2_2") (pintype "passive"))
      (node (ref "U6") (pin "31") (pinfunction "PD1(TXD)_31") (pintype "bidirectional"))
    )
    (net (code "100") (name "Net-(U6-PD2(INT0))") (class "Default")
      (node (ref "R31") (pin "2") (pinfunction "2_2") (pintype "passive"))
      (node (ref "U6") (pin "32") (pinfunction "PD2(INT0)_32") (pintype "bidirectional"))
    )
    (net (code "101") (name "Net-(U6-PD3(INT1))") (class "Default")
      (node (ref "R32") (pin "2") (pinfunction "2_2") (pintype "passive"))
      (node (ref "U6") (pin "1") (pinfunction "PD3(INT1)_1") (pintype "bidirectional"))
    )
    (net (code "102") (name "Net-(U6-PD4(XCK{slash}T0))") (class "Default")
      (node (ref "R33") (pin "2") (pinfunction "2_2") (pintype "passive"))
      (node (ref "U6") (pin "2") (pinfunction "PD4(XCK/T0)_2") (pintype "bidirectional"))
    )
    (net (code "103") (name "Net-(U6-PD5(T1))") (class "Default")
      (node (ref "R34") (pin "2") (pinfunction "2_2") (pintype "passive"))
      (node (ref "U6") (pin "9") (pinfunction "PD5(T1)_9") (pintype "bidirectional"))
    )
    (net (code "104") (name "PURGE_V") (class "Default")
      (node (ref "M1") (pin "IN2") (pinfunction "IN2_IN2") (pintype "bidirectional"))
      (node (ref "T1") (pin "9") (pinfunction "9/RX2/PWM_9") (pintype "bidirectional"))
    )
    (net (code "105") (name "PURGE_V_G") (class "Default")
      (node (ref "ETH6") (pin "P$4") (pinfunction "4_P$4") (pintype "bidirectional"))
      (node (ref "M1") (pin "OUT2") (pinfunction "OUT2_OUT2") (pintype "bidirectional"))
      (node (ref "R16") (pin "2") (pinfunction "2_2") (pintype "passive"))
    )
    (net (code "106") (name "RX1") (class "Default")
      (node (ref "CAN1") (pin "TX0") (pinfunction "TX0_TX0") (pintype "bidirectional"))
      (node (ref "T1") (pin "0") (pinfunction "0/RX1/T_0") (pintype "bidirectional"))
    )
    (net (code "107") (name "RX3") (class "Default")
      (node (ref "O1") (pin "P$3") (pinfunction "TXO_P$3") (pintype "bidirectional"))
      (node (ref "T1") (pin "7") (pinfunction "7/RX3_7") (pintype "bidirectional"))
    )
    (net (code "108") (name "SCK1") (class "Default")
      (node (ref "ISP1") (pin "3") (pinfunction "SCK_3") (pintype "output"))
      (node (ref "U3") (pin "17") (pinfunction "PB5(SCK)_17") (pintype "bidirectional"))
    )
    (net (code "109") (name "SCK2") (class "Default")
      (node (ref "ISP2") (pin "3") (pinfunction "SCK_3") (pintype "output"))
      (node (ref "U4") (pin "17") (pinfunction "PB5(SCK)_17") (pintype "bidirectional"))
    )
    (net (code "110") (name "SCK3") (class "Default")
      (node (ref "ISP3") (pin "3") (pinfunction "SCK_3") (pintype "output"))
      (node (ref "U6") (pin "17") (pinfunction "PB5(SCK)_17") (pintype "bidirectional"))
    )
    (net (code "111") (name "SCL") (class "Default")
      (node (ref "FAN1") (pin "SCL") (pinfunction "SCL_SCL") (pintype "bidirectional"))
      (node (ref "LCD1") (pin "SCL") (pinfunction "SCL_SCL") (pintype "bidirectional"))
      (node (ref "R3") (pin "2") (pinfunction "2_2") (pintype "passive"))
      (node (ref "RTC1") (pin "P$3") (pinfunction "SCL_P$3") (pintype "bidirectional"))
      (node (ref "SHT1") (pin "SCL") (pinfunction "SCL_SCL") (pintype "bidirectional"))
      (node (ref "T1") (pin "19/A5") (pinfunction "19/A5/T/SCL0_19/A5") (pintype "bidirectional"))
      (node (ref "U3") (pin "28") (pinfunction "PC5(ADC5/SCL)_28") (pintype "bidirectional"))
      (node (ref "U4") (pin "28") (pinfunction "PC5(ADC5/SCL)_28") (pintype "bidirectional"))
      (node (ref "U6") (pin "28") (pinfunction "PC5(ADC5/SCL)_28") (pintype "bidirectional"))
    )
    (net (code "112") (name "SDA") (class "Default")
      (node (ref "FAN1") (pin "SDA") (pinfunction "SDA_SDA") (pintype "bidirectional"))
      (node (ref "LCD1") (pin "SDA") (pinfunction "SDA_SDA") (pintype "bidirectional"))
      (node (ref "R4") (pin "2") (pinfunction "2_2") (pintype "passive"))
      (node (ref "RTC1") (pin "P$4") (pinfunction "SDA_P$4") (pintype "bidirectional"))
      (node (ref "SHT1") (pin "SDA") (pinfunction "SDA_SDA") (pintype "bidirectional"))
      (node (ref "T1") (pin "18/A4") (pinfunction "18/A4/T/SDA0_18/A4") (pintype "bidirectional"))
      (node (ref "U3") (pin "27") (pinfunction "PC4(ADC4/SDA)_27") (pintype "bidirectional"))
      (node (ref "U4") (pin "27") (pinfunction "PC4(ADC4/SDA)_27") (pintype "bidirectional"))
      (node (ref "U6") (pin "27") (pinfunction "PC4(ADC4/SDA)_27") (pintype "bidirectional"))
    )
    (net (code "113") (name "START_R") (class "Default")
      (node (ref "IC1") (pin "1") (pinfunction "I0_1") (pintype "input"))
      (node (ref "T1") (pin "21/A7") (pinfunction "21/A7/PWM_21/A7") (pintype "bidirectional"))
    )
    (net (code "114") (name "START_R_OUT") (class "Default")
      (node (ref "ETH1") (pin "P$1") (pinfunction "1_P$1") (pintype "bidirectional"))
      (node (ref "IC1") (pin "3") (pinfunction "O_3") (pintype "output"))
    )
    (net (code "115") (name "SUPPLY_V") (class "Default")
      (node (ref "M1") (pin "IN1") (pinfunction "IN1_IN1") (pintype "bidirectional"))
      (node (ref "T1") (pin "6") (pinfunction "6/PWM_6") (pintype "bidirectional"))
    )
    (net (code "116") (name "SUPPLY_V_G") (class "Default")
      (node (ref "ETH6") (pin "P$2") (pinfunction "2_P$2") (pintype "bidirectional"))
      (node (ref "M1") (pin "OUT1") (pinfunction "OUT1_OUT1") (pintype "bidirectional"))
      (node (ref "R17") (pin "2") (pinfunction "2_2") (pintype "passive"))
    )
    (net (code "117") (name "THIS_IS_NOT_CONNECTED_1") (class "Default")
      (node (ref "ISP1") (pin "2") (pinfunction "VCC_2") (pintype "power_in"))
    )
    (net (code "118") (name "THIS_IS_NOT_CONNECTED_2") (class "Default")
      (node (ref "ISP2") (pin "2") (pinfunction "VCC_2") (pintype "power_in"))
    )
    (net (code "119") (name "THIS_IS_NOT_CONNECTED_3") (class "Default")
      (node (ref "ISP3") (pin "2") (pinfunction "VCC_2") (pintype "power_in"))
    )
    (net (code "120") (name "TX1") (class "Default")
      (node (ref "CAN1") (pin "RXI") (pinfunction "RXI_RXI") (pintype "bidirectional"))
      (node (ref "T1") (pin "1") (pinfunction "1/TX1/T_1") (pintype "bidirectional"))
    )
    (net (code "121") (name "TX3") (class "Default")
      (node (ref "O1") (pin "P$2") (pinfunction "RXI_P$2") (pintype "bidirectional"))
      (node (ref "T1") (pin "8") (pinfunction "8/TX3_8") (pintype "bidirectional"))
    )
    (net (code "122") (name "VBAT") (class "Default")
      (node (ref "T1") (pin "VBAT") (pinfunction "VBAT_VBAT") (pintype "power_in"))
    )
    (net (code "123") (name "VDD") (class "Default")
      (node (ref "SJ2") (pin "2") (pinfunction "2_2") (pintype "passive"))
    )
    (net (code "124") (name "VSS") (class "Default")
      (node (ref "SJ1") (pin "2") (pinfunction "2_2") (pintype "passive"))
    )
    (net (code "125") (name "VUSB") (class "Default")
      (node (ref "T1") (pin "VUSB") (pinfunction "VUSB_VUSB") (pintype "power_in"))
    )
    (net (code "126") (name "unconnected-(CAN1-PadCTS)") (class "Default")
      (node (ref "CAN1") (pin "CTS") (pinfunction "CTS_CTS") (pintype "bidirectional"))
    )
    (net (code "127") (name "unconnected-(CAN1-PadDTR)") (class "Default")
      (node (ref "CAN1") (pin "DTR") (pinfunction "DTR_DTR") (pintype "bidirectional"))
    )
    (net (code "128") (name "unconnected-(CAN1-PadSCL)") (class "Default")
      (node (ref "CAN1") (pin "SCL") (pinfunction "SCL_SCL") (pintype "bidirectional"))
    )
    (net (code "129") (name "unconnected-(CAN1-PadSDA)") (class "Default")
      (node (ref "CAN1") (pin "SDA") (pinfunction "SDA_SDA") (pintype "bidirectional"))
    )
    (net (code "130") (name "unconnected-(CAN1-PadVIN)") (class "Default")
      (node (ref "CAN1") (pin "VIN") (pinfunction "VIN_VIN") (pintype "bidirectional"))
    )
    (net (code "131") (name "unconnected-(ETH1-LED1N-PadP$9)") (class "Default")
      (node (ref "ETH1") (pin "P$9") (pinfunction "LED1N_P$9") (pintype "bidirectional"))
    )
    (net (code "132") (name "unconnected-(ETH1-LED1P-PadP$10)") (class "Default")
      (node (ref "ETH1") (pin "P$10") (pinfunction "LED1P_P$10") (pintype "bidirectional"))
    )
    (net (code "133") (name "unconnected-(ETH1-LED2N-PadP$11)") (class "Default")
      (node (ref "ETH1") (pin "P$11") (pinfunction "LED2N_P$11") (pintype "bidirectional"))
    )
    (net (code "134") (name "unconnected-(ETH1-LED2P-PadP$12)") (class "Default")
      (node (ref "ETH1") (pin "P$12") (pinfunction "LED2P_P$12") (pintype "bidirectional"))
    )
    (net (code "135") (name "unconnected-(ETH2-LED1N-PadP$9)") (class "Default")
      (node (ref "ETH2") (pin "P$9") (pinfunction "LED1N_P$9") (pintype "bidirectional"))
    )
    (net (code "136") (name "unconnected-(ETH2-LED1P-PadP$10)") (class "Default")
      (node (ref "ETH2") (pin "P$10") (pinfunction "LED1P_P$10") (pintype "bidirectional"))
    )
    (net (code "137") (name "unconnected-(ETH2-LED2N-PadP$11)") (class "Default")
      (node (ref "ETH2") (pin "P$11") (pinfunction "LED2N_P$11") (pintype "bidirectional"))
    )
    (net (code "138") (name "unconnected-(ETH2-LED2P-PadP$12)") (class "Default")
      (node (ref "ETH2") (pin "P$12") (pinfunction "LED2P_P$12") (pintype "bidirectional"))
    )
    (net (code "139") (name "unconnected-(ETH3-LED1N-PadP$9)") (class "Default")
      (node (ref "ETH3") (pin "P$9") (pinfunction "LED1N_P$9") (pintype "bidirectional"))
    )
    (net (code "140") (name "unconnected-(ETH3-LED1P-PadP$10)") (class "Default")
      (node (ref "ETH3") (pin "P$10") (pinfunction "LED1P_P$10") (pintype "bidirectional"))
    )
    (net (code "141") (name "unconnected-(ETH3-LED2N-PadP$11)") (class "Default")
      (node (ref "ETH3") (pin "P$11") (pinfunction "LED2N_P$11") (pintype "bidirectional"))
    )
    (net (code "142") (name "unconnected-(ETH3-LED2P-PadP$12)") (class "Default")
      (node (ref "ETH3") (pin "P$12") (pinfunction "LED2P_P$12") (pintype "bidirectional"))
    )
    (net (code "143") (name "unconnected-(ETH4-3-PadP$3)") (class "Default")
      (node (ref "ETH4") (pin "P$3") (pinfunction "3_P$3") (pintype "bidirectional"))
    )
    (net (code "144") (name "unconnected-(ETH4-4-PadP$4)") (class "Default")
      (node (ref "ETH4") (pin "P$4") (pinfunction "4_P$4") (pintype "bidirectional"))
    )
    (net (code "145") (name "unconnected-(ETH4-5-PadP$5)") (class "Default")
      (node (ref "ETH4") (pin "P$5") (pinfunction "5_P$5") (pintype "bidirectional"))
    )
    (net (code "146") (name "unconnected-(ETH4-LED1N-PadP$9)") (class "Default")
      (node (ref "ETH4") (pin "P$9") (pinfunction "LED1N_P$9") (pintype "bidirectional"))
    )
    (net (code "147") (name "unconnected-(ETH4-LED1P-PadP$10)") (class "Default")
      (node (ref "ETH4") (pin "P$10") (pinfunction "LED1P_P$10") (pintype "bidirectional"))
    )
    (net (code "148") (name "unconnected-(ETH4-LED2N-PadP$11)") (class "Default")
      (node (ref "ETH4") (pin "P$11") (pinfunction "LED2N_P$11") (pintype "bidirectional"))
    )
    (net (code "149") (name "unconnected-(ETH4-LED2P-PadP$12)") (class "Default")
      (node (ref "ETH4") (pin "P$12") (pinfunction "LED2P_P$12") (pintype "bidirectional"))
    )
    (net (code "150") (name "unconnected-(ETH5-4-PadP$4)") (class "Default")
      (node (ref "ETH5") (pin "P$4") (pinfunction "4_P$4") (pintype "bidirectional"))
    )
    (net (code "151") (name "unconnected-(ETH5-5-PadP$5)") (class "Default")
      (node (ref "ETH5") (pin "P$5") (pinfunction "5_P$5") (pintype "bidirectional"))
    )
    (net (code "152") (name "unconnected-(ETH5-6-PadP$6)") (class "Default")
      (node (ref "ETH5") (pin "P$6") (pinfunction "6_P$6") (pintype "bidirectional"))
    )
    (net (code "153") (name "unconnected-(ETH5-7-PadP$7)") (class "Default")
      (node (ref "ETH5") (pin "P$7") (pinfunction "7_P$7") (pintype "bidirectional"))
    )
    (net (code "154") (name "unconnected-(ETH5-8-PadP$8)") (class "Default")
      (node (ref "ETH5") (pin "P$8") (pinfunction "8_P$8") (pintype "bidirectional"))
    )
    (net (code "155") (name "unconnected-(ETH5-LED1N-PadP$9)") (class "Default")
      (node (ref "ETH5") (pin "P$9") (pinfunction "LED1N_P$9") (pintype "bidirectional"))
    )
    (net (code "156") (name "unconnected-(ETH5-LED1P-PadP$10)") (class "Default")
      (node (ref "ETH5") (pin "P$10") (pinfunction "LED1P_P$10") (pintype "bidirectional"))
    )
    (net (code "157") (name "unconnected-(ETH5-LED2N-PadP$11)") (class "Default")
      (node (ref "ETH5") (pin "P$11") (pinfunction "LED2N_P$11") (pintype "bidirectional"))
    )
    (net (code "158") (name "unconnected-(ETH5-LED2P-PadP$12)") (class "Default")
      (node (ref "ETH5") (pin "P$12") (pinfunction "LED2P_P$12") (pintype "bidirectional"))
    )
    (net (code "159") (name "unconnected-(ETH6-7-PadP$7)") (class "Default")
      (node (ref "ETH6") (pin "P$7") (pinfunction "7_P$7") (pintype "bidirectional"))
    )
    (net (code "160") (name "unconnected-(ETH6-8-PadP$8)") (class "Default")
      (node (ref "ETH6") (pin "P$8") (pinfunction "8_P$8") (pintype "bidirectional"))
    )
    (net (code "161") (name "unconnected-(ETH6-LED1N-PadP$9)") (class "Default")
      (node (ref "ETH6") (pin "P$9") (pinfunction "LED1N_P$9") (pintype "bidirectional"))
    )
    (net (code "162") (name "unconnected-(ETH6-LED1P-PadP$10)") (class "Default")
      (node (ref "ETH6") (pin "P$10") (pinfunction "LED1P_P$10") (pintype "bidirectional"))
    )
    (net (code "163") (name "unconnected-(ETH6-LED2N-PadP$11)") (class "Default")
      (node (ref "ETH6") (pin "P$11") (pinfunction "LED2N_P$11") (pintype "bidirectional"))
    )
    (net (code "164") (name "unconnected-(ETH6-LED2P-PadP$12)") (class "Default")
      (node (ref "ETH6") (pin "P$12") (pinfunction "LED2P_P$12") (pintype "bidirectional"))
    )
    (net (code "165") (name "unconnected-(ETH7-3-PadP$3)") (class "Default")
      (node (ref "ETH7") (pin "P$3") (pinfunction "3_P$3") (pintype "bidirectional"))
    )
    (net (code "166") (name "unconnected-(ETH7-4-PadP$4)") (class "Default")
      (node (ref "ETH7") (pin "P$4") (pinfunction "4_P$4") (pintype "bidirectional"))
    )
    (net (code "167") (name "unconnected-(ETH7-7-PadP$7)") (class "Default")
      (node (ref "ETH7") (pin "P$7") (pinfunction "7_P$7") (pintype "bidirectional"))
    )
    (net (code "168") (name "unconnected-(ETH7-LED1N-PadP$9)") (class "Default")
      (node (ref "ETH7") (pin "P$9") (pinfunction "LED1N_P$9") (pintype "bidirectional"))
    )
    (net (code "169") (name "unconnected-(ETH7-LED1P-PadP$10)") (class "Default")
      (node (ref "ETH7") (pin "P$10") (pinfunction "LED1P_P$10") (pintype "bidirectional"))
    )
    (net (code "170") (name "unconnected-(ETH7-LED2N-PadP$11)") (class "Default")
      (node (ref "ETH7") (pin "P$11") (pinfunction "LED2N_P$11") (pintype "bidirectional"))
    )
    (net (code "171") (name "unconnected-(ETH7-LED2P-PadP$12)") (class "Default")
      (node (ref "ETH7") (pin "P$12") (pinfunction "LED2P_P$12") (pintype "bidirectional"))
    )
    (net (code "172") (name "unconnected-(O1-DTR-PadP$1)") (class "Default")
      (node (ref "O1") (pin "P$1") (pinfunction "DTR_P$1") (pintype "bidirectional"))
    )
    (net (code "173") (name "unconnected-(RTC1-32KHZ-PadP$6)") (class "Default")
      (node (ref "RTC1") (pin "P$6") (pinfunction "32KHZ_P$6") (pintype "bidirectional"))
    )
    (net (code "174") (name "unconnected-(RTC1-BAT-PadP$5)") (class "Default")
      (node (ref "RTC1") (pin "P$5") (pinfunction "BAT_P$5") (pintype "bidirectional"))
    )
    (net (code "175") (name "unconnected-(RTC1-RST-PadP$8)") (class "Default")
      (node (ref "RTC1") (pin "P$8") (pinfunction "RST_P$8") (pintype "bidirectional"))
    )
    (net (code "176") (name "unconnected-(RTC1-SQW-PadP$7)") (class "Default")
      (node (ref "RTC1") (pin "P$7") (pinfunction "SQW_P$7") (pintype "bidirectional"))
    )
    (net (code "177") (name "unconnected-(SHT1-ADDR-PadADR)") (class "Default")
      (node (ref "SHT1") (pin "ADR") (pinfunction "ADDR_ADR") (pintype "bidirectional"))
    )
    (net (code "178") (name "unconnected-(SHT1-ALERT-PadALR)") (class "Default")
      (node (ref "SHT1") (pin "ALR") (pinfunction "ALERT_ALR") (pintype "bidirectional"))
    )
    (net (code "179") (name "unconnected-(SHT1-PadRST)") (class "Default")
      (node (ref "SHT1") (pin "RST") (pinfunction "RST_RST") (pintype "bidirectional"))
    )
    (net (code "180") (name "unconnected-(T1-13{slash}SCK{slash}LED-Pad13)") (class "Default")
      (node (ref "T1") (pin "13") (pinfunction "13/SCK/LED_13") (pintype "bidirectional"))
    )
    (net (code "181") (name "unconnected-(T1-23{slash}A9{slash}T{slash}PWM-Pad23{slash}A9)") (class "Default")
      (node (ref "T1") (pin "23/A9") (pinfunction "23/A9/T/PWM_23/A9") (pintype "bidirectional"))
    )
    (net (code "182") (name "unconnected-(T1-A14{slash}DAC-PadRESET{slash}DAC)") (class "Default")
      (node (ref "T1") (pin "RESET/DAC") (pinfunction "A14/DAC_RESET/DAC") (pintype "bidirectional"))
    )
    (net (code "183") (name "unconnected-(T1-PadA10)") (class "Default")
      (node (ref "T1") (pin "A10") (pinfunction "A10_A10") (pintype "bidirectional"))
    )
    (net (code "184") (name "unconnected-(T1-PadPGM)") (class "Default")
      (node (ref "T1") (pin "PGM") (pinfunction "PGM_PGM") (pintype "bidirectional"))
    )
    (net (code "185") (name "unconnected-(U3-ADC6-Pad19)") (class "Default")
      (node (ref "U3") (pin "19") (pinfunction "ADC6_19") (pintype "bidirectional"))
    )
    (net (code "186") (name "unconnected-(U3-ADC7-Pad22)") (class "Default")
      (node (ref "U3") (pin "22") (pinfunction "ADC7_22") (pintype "bidirectional"))
    )
    (net (code "187") (name "unconnected-(U3-PB0(ICP)-Pad12)") (class "Default")
      (node (ref "U3") (pin "12") (pinfunction "PB0(ICP)_12") (pintype "bidirectional"))
    )
    (net (code "188") (name "unconnected-(U3-PB1(OC1A)-Pad13)") (class "Default")
      (node (ref "U3") (pin "13") (pinfunction "PB1(OC1A)_13") (pintype "bidirectional"))
    )
    (net (code "189") (name "unconnected-(U3-PB2(SS{slash}OC1B)-Pad14)") (class "Default")
      (node (ref "U3") (pin "14") (pinfunction "PB2(SS/OC1B)_14") (pintype "bidirectional"))
    )
    (net (code "190") (name "unconnected-(U3-PC0(ADC0)-Pad23)") (class "Default")
      (node (ref "U3") (pin "23") (pinfunction "PC0(ADC0)_23") (pintype "bidirectional"))
    )
    (net (code "191") (name "unconnected-(U3-PC1(ADC1)-Pad24)") (class "Default")
      (node (ref "U3") (pin "24") (pinfunction "PC1(ADC1)_24") (pintype "bidirectional"))
    )
    (net (code "192") (name "unconnected-(U3-PC2(ADC2)-Pad25)") (class "Default")
      (node (ref "U3") (pin "25") (pinfunction "PC2(ADC2)_25") (pintype "bidirectional"))
    )
    (net (code "193") (name "unconnected-(U3-PC3(ADC3)-Pad26)") (class "Default")
      (node (ref "U3") (pin "26") (pinfunction "PC3(ADC3)_26") (pintype "bidirectional"))
    )
    (net (code "194") (name "unconnected-(U3-PD2(INT0)-Pad32)") (class "Default")
      (node (ref "U3") (pin "32") (pinfunction "PD2(INT0)_32") (pintype "bidirectional"))
    )
    (net (code "195") (name "unconnected-(U3-PD4(XCK{slash}T0)-Pad2)") (class "Default")
      (node (ref "U3") (pin "2") (pinfunction "PD4(XCK/T0)_2") (pintype "bidirectional"))
    )
    (net (code "196") (name "unconnected-(U3-PD5(T1)-Pad9)") (class "Default")
      (node (ref "U3") (pin "9") (pinfunction "PD5(T1)_9") (pintype "bidirectional"))
    )
    (net (code "197") (name "unconnected-(U3-PD6(AIN0)-Pad10)") (class "Default")
      (node (ref "U3") (pin "10") (pinfunction "PD6(AIN0)_10") (pintype "bidirectional"))
    )
    (net (code "198") (name "unconnected-(U3-PD7(AIN1)-Pad11)") (class "Default")
      (node (ref "U3") (pin "11") (pinfunction "PD7(AIN1)_11") (pintype "bidirectional"))
    )
    (net (code "199") (name "unconnected-(U4-ADC6-Pad19)") (class "Default")
      (node (ref "U4") (pin "19") (pinfunction "ADC6_19") (pintype "bidirectional"))
    )
    (net (code "200") (name "unconnected-(U4-ADC7-Pad22)") (class "Default")
      (node (ref "U4") (pin "22") (pinfunction "ADC7_22") (pintype "bidirectional"))
    )
    (net (code "201") (name "unconnected-(U4-PB0(ICP)-Pad12)") (class "Default")
      (node (ref "U4") (pin "12") (pinfunction "PB0(ICP)_12") (pintype "bidirectional"))
    )
    (net (code "202") (name "unconnected-(U4-PB1(OC1A)-Pad13)") (class "Default")
      (node (ref "U4") (pin "13") (pinfunction "PB1(OC1A)_13") (pintype "bidirectional"))
    )
    (net (code "203") (name "unconnected-(U4-PB2(SS{slash}OC1B)-Pad14)") (class "Default")
      (node (ref "U4") (pin "14") (pinfunction "PB2(SS/OC1B)_14") (pintype "bidirectional"))
    )
    (net (code "204") (name "unconnected-(U4-PC0(ADC0)-Pad23)") (class "Default")
      (node (ref "U4") (pin "23") (pinfunction "PC0(ADC0)_23") (pintype "bidirectional"))
    )
    (net (code "205") (name "unconnected-(U4-PC1(ADC1)-Pad24)") (class "Default")
      (node (ref "U4") (pin "24") (pinfunction "PC1(ADC1)_24") (pintype "bidirectional"))
    )
    (net (code "206") (name "unconnected-(U4-PC2(ADC2)-Pad25)") (class "Default")
      (node (ref "U4") (pin "25") (pinfunction "PC2(ADC2)_25") (pintype "bidirectional"))
    )
    (net (code "207") (name "unconnected-(U4-PC3(ADC3)-Pad26)") (class "Default")
      (node (ref "U4") (pin "26") (pinfunction "PC3(ADC3)_26") (pintype "bidirectional"))
    )
    (net (code "208") (name "unconnected-(U4-PD2(INT0)-Pad32)") (class "Default")
      (node (ref "U4") (pin "32") (pinfunction "PD2(INT0)_32") (pintype "bidirectional"))
    )
    (net (code "209") (name "unconnected-(U4-PD4(XCK{slash}T0)-Pad2)") (class "Default")
      (node (ref "U4") (pin "2") (pinfunction "PD4(XCK/T0)_2") (pintype "bidirectional"))
    )
    (net (code "210") (name "unconnected-(U4-PD5(T1)-Pad9)") (class "Default")
      (node (ref "U4") (pin "9") (pinfunction "PD5(T1)_9") (pintype "bidirectional"))
    )
    (net (code "211") (name "unconnected-(U4-PD6(AIN0)-Pad10)") (class "Default")
      (node (ref "U4") (pin "10") (pinfunction "PD6(AIN0)_10") (pintype "bidirectional"))
    )
    (net (code "212") (name "unconnected-(U4-PD7(AIN1)-Pad11)") (class "Default")
      (node (ref "U4") (pin "11") (pinfunction "PD7(AIN1)_11") (pintype "bidirectional"))
    )
    (net (code "213") (name "unconnected-(U6-PB0(ICP)-Pad12)") (class "Default")
      (node (ref "U6") (pin "12") (pinfunction "PB0(ICP)_12") (pintype "bidirectional"))
    )
    (net (code "214") (name "unconnected-(U6-PB1(OC1A)-Pad13)") (class "Default")
      (node (ref "U6") (pin "13") (pinfunction "PB1(OC1A)_13") (pintype "bidirectional"))
    )
    (net (code "215") (name "unconnected-(U6-PB2(SS{slash}OC1B)-Pad14)") (class "Default")
      (node (ref "U6") (pin "14") (pinfunction "PB2(SS/OC1B)_14") (pintype "bidirectional"))
    )
    (net (code "216") (name "unconnected-(U6-PB6(XTAL1{slash}TOSC1)-Pad7)") (class "Default")
      (node (ref "U6") (pin "7") (pinfunction "PB6(XTAL1/TOSC1)_7") (pintype "bidirectional"))
    )
    (net (code "217") (name "unconnected-(U6-PB7(XTAL2{slash}TOSC2)-Pad8)") (class "Default")
      (node (ref "U6") (pin "8") (pinfunction "PB7(XTAL2/TOSC2)_8") (pintype "bidirectional"))
    )
    (net (code "218") (name "unconnected-(U6-PD6(AIN0)-Pad10)") (class "Default")
      (node (ref "U6") (pin "10") (pinfunction "PD6(AIN0)_10") (pintype "bidirectional"))
    )
    (net (code "219") (name "unconnected-(U6-PD7(AIN1)-Pad11)") (class "Default")
      (node (ref "U6") (pin "11") (pinfunction "PD7(AIN1)_11") (pintype "bidirectional"))
    )
  )
)
